# Relay_Scch.net
KiCad netlist of a schematic drawn in Altium Designer
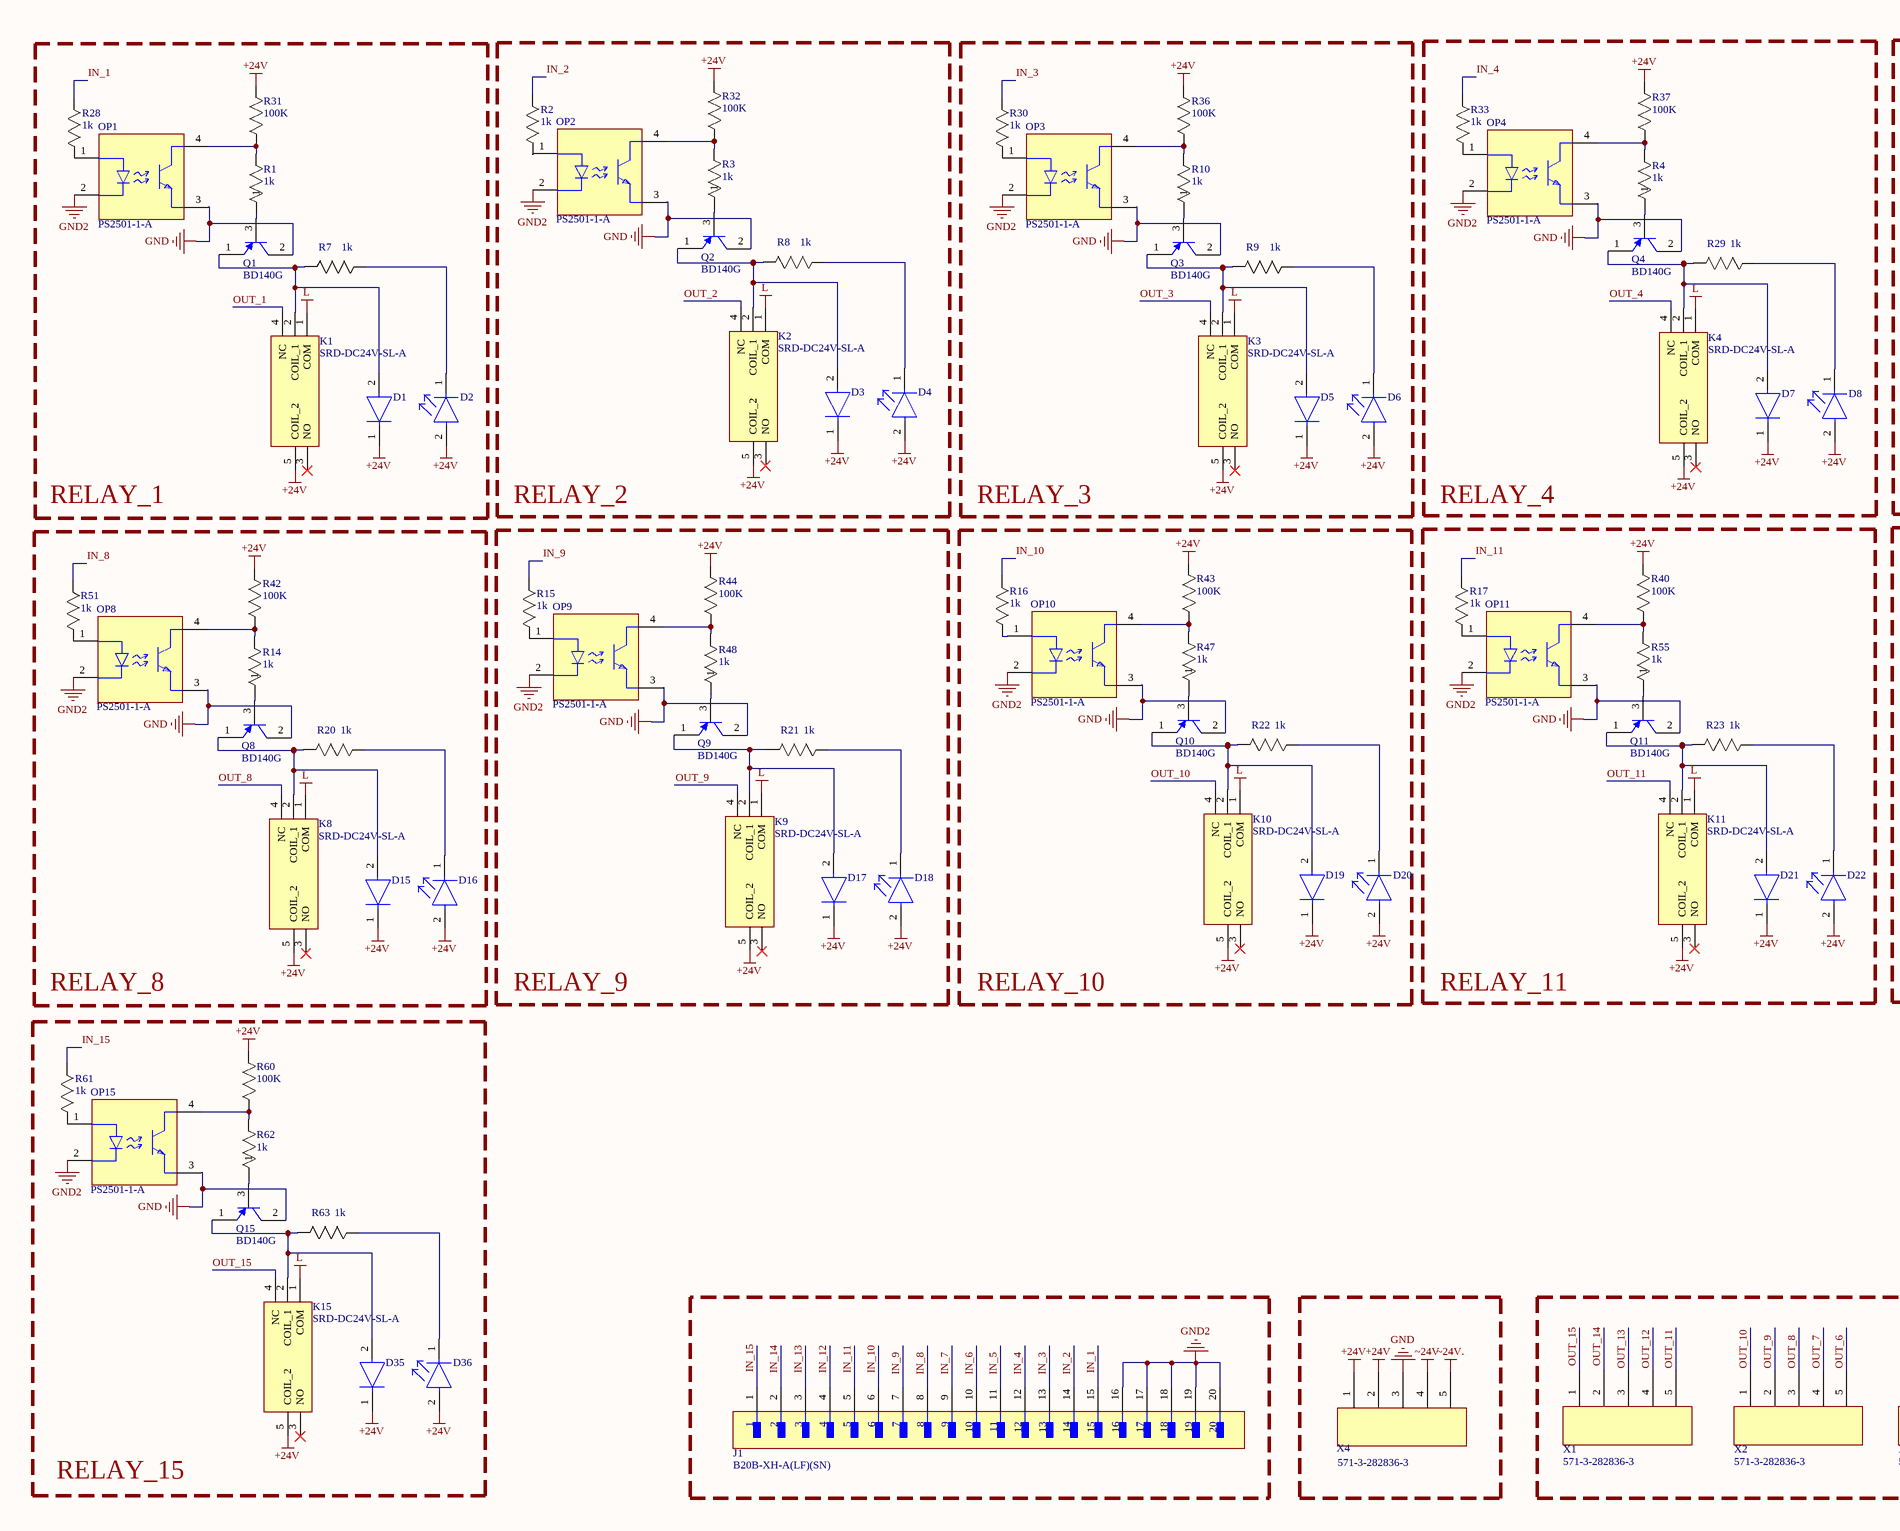
[diagram p0: Relay_Scch.SchDoc, left]
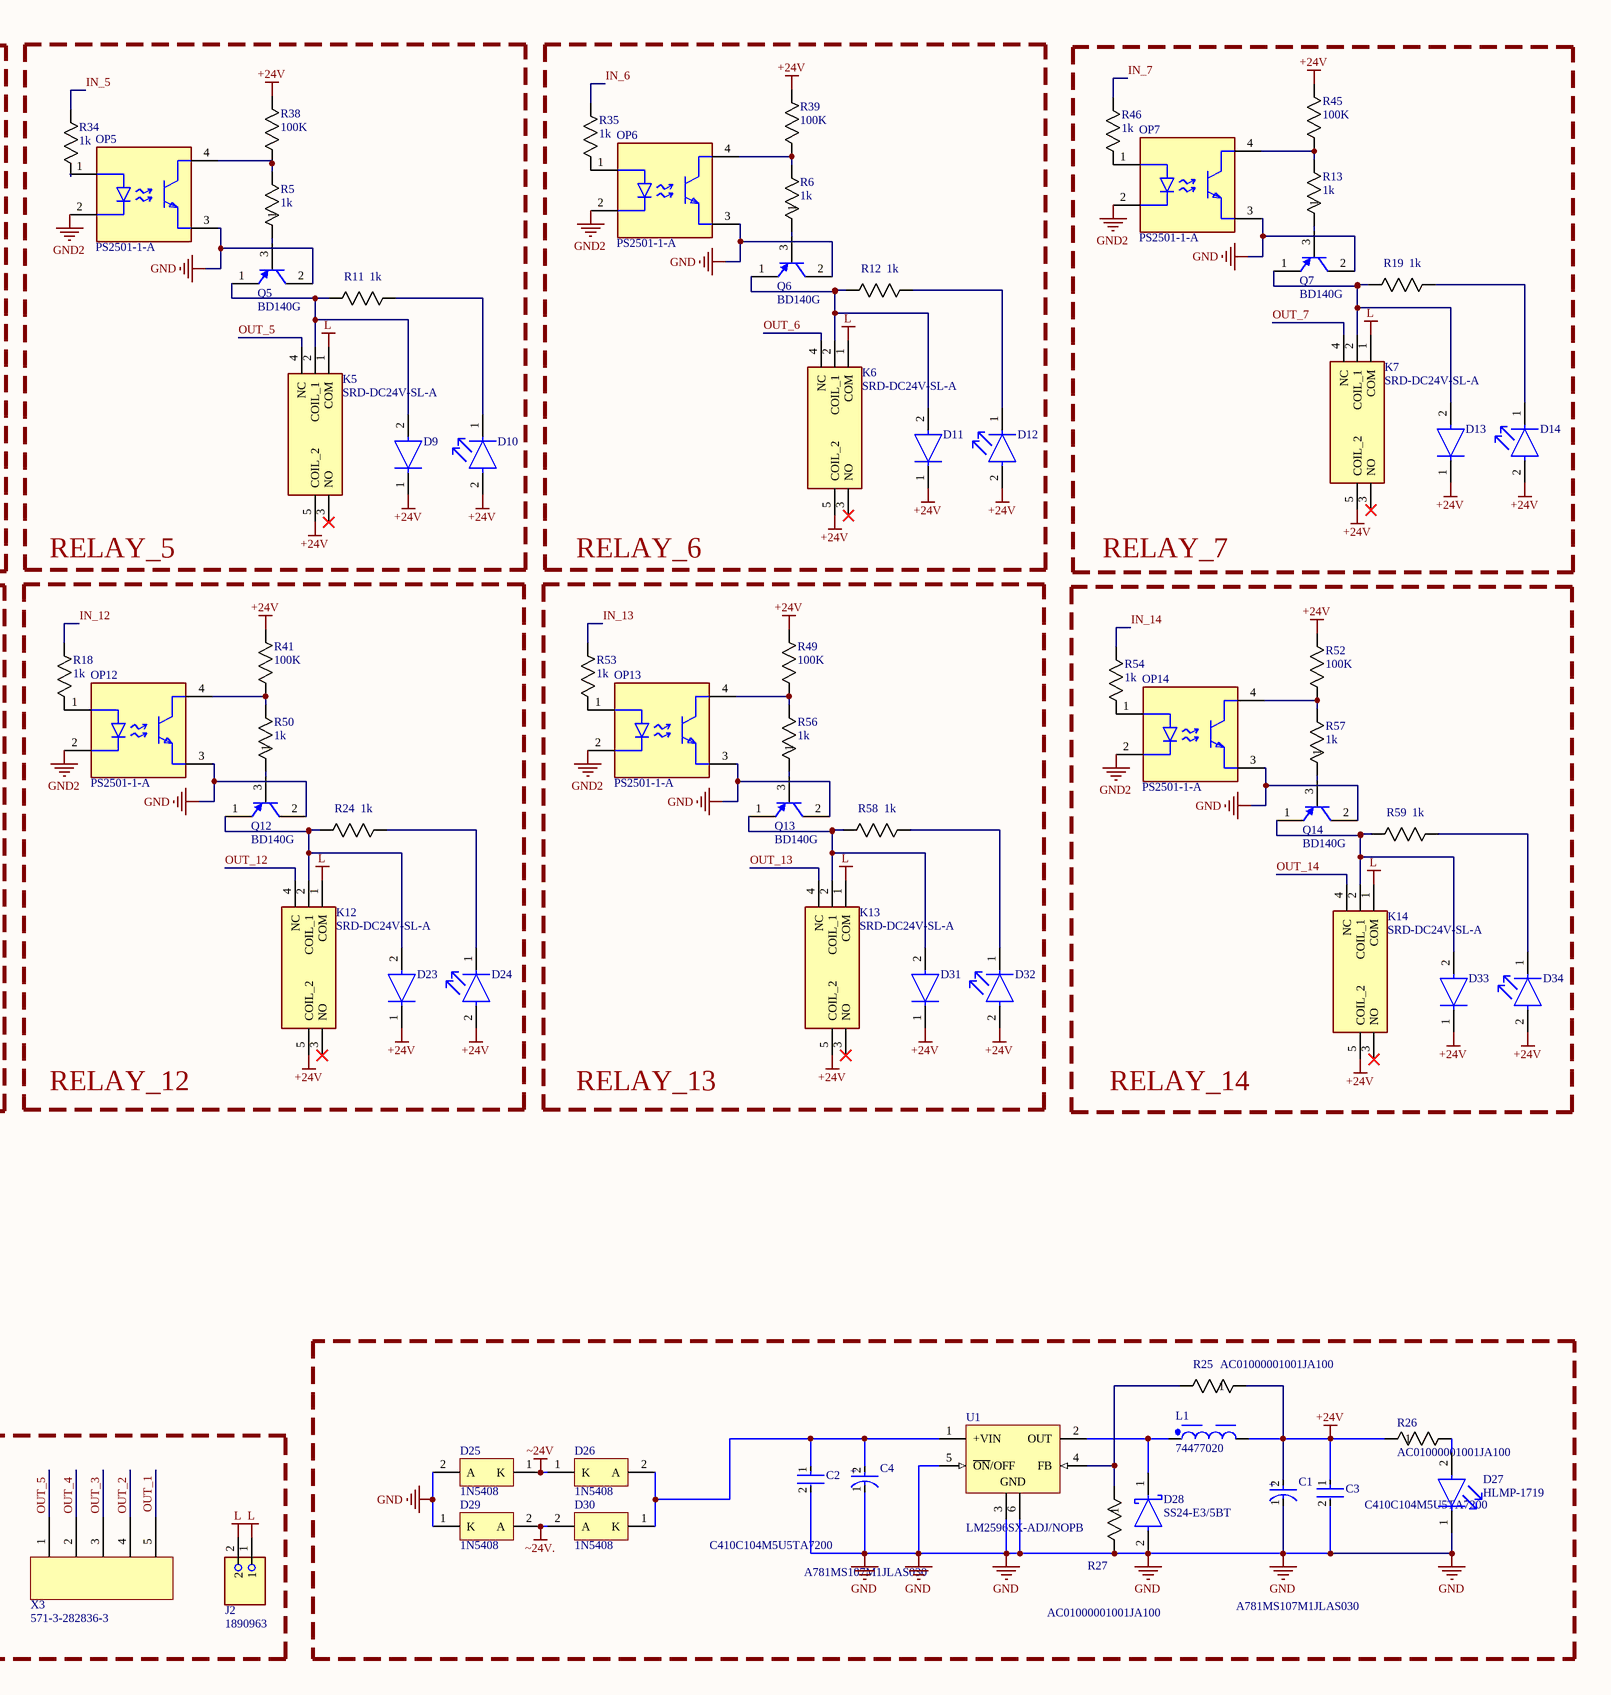
[diagram p1: Relay_Scch.SchDoc, right]

(export (version "E")
  (design (tool "Eeschema 10.0.6"))
  (components
    (comp (ref "C1")
      (value "A781MS107M1JLAS030")
      (footprint "FP-A781MS-S-MFG")
      (description "HYBRID POLYMER, V-CHIP, AEC-Q200")
      (libsource (lib "Altium Content Vault") (part "cf48714ba7e38822c1575c7ec0b6d1f"))
    )
    (comp (ref "C2")
      (value "C410C104M5U5TA7200")
      (footprint "FP-C410C104M5U5TA7200-MFG")
      (description "CAP CER 0.1UF 50V Z5U AXIAL")
      (fields (field (name "TOLERANCE") "20%"))
      (libsource (lib "Altium Content Vault") (part "b4654b650e69147ec39a6b967a45e02"))
    )
    (comp (ref "C3")
      (value "C410C104M5U5TA7200")
      (footprint "FP-C410C104M5U5TA7200-MFG")
      (description "CAP CER 0.1UF 50V Z5U AXIAL")
      (fields (field (name "TOLERANCE") "20%"))
      (libsource (lib "Altium Content Vault") (part "b4654b650e69147ec39a6b967a45e02"))
    )
    (comp (ref "C4")
      (value "A781MS107M1JLAS030")
      (footprint "FP-A781MS-S-MFG")
      (description "HYBRID POLYMER, V-CHIP, AEC-Q200")
      (libsource (lib "Altium Content Vault") (part "cf48714ba7e38822c1575c7ec0b6d1f"))
    )
    (comp (ref "D1")
      (value "1N4007")
      (footprint "FP-1N4007-MFG")
      (description "Rectifier diode 1000 V 1 A DO-41, ,")
      (fields
        (field (name "MANUFACTURER") "Diotec")
        (field (name "OCTOPART") "https://octopart.com/1n4007-diotec-4040411")
      )
      (libsource (lib "Altium Content Vault") (part "d7152d700b627762746794eb795d46e"))
    )
    (comp (ref "D2")
      (value "HLMP-1719")
      (footprint "FP-HLMP-1719-MFG")
      (description "LED YELLOW DIFFUSED T-1 T/H")
      (fields
        (field (name "MANUFACTURER") "Broadcom")
        (field (name "OCTOPART") "https://octopart.com/hlmp-1719-broadcom-71130405")
      )
      (libsource (lib "Altium Content Vault") (part "8706943c75ba83719d021d2fdc84c58"))
    )
    (comp (ref "D3")
      (value "1N4007")
      (footprint "FP-1N4007-MFG")
      (description "Rectifier diode 1000 V 1 A DO-41, ,")
      (fields
        (field (name "MANUFACTURER") "Diotec")
        (field (name "OCTOPART") "https://octopart.com/1n4007-diotec-4040411")
      )
      (libsource (lib "Altium Content Vault") (part "d7152d700b627762746794eb795d46e"))
    )
    (comp (ref "D4")
      (value "HLMP-1719")
      (footprint "FP-HLMP-1719-MFG")
      (description "LED YELLOW DIFFUSED T-1 T/H")
      (fields
        (field (name "MANUFACTURER") "Broadcom")
        (field (name "OCTOPART") "https://octopart.com/hlmp-1719-broadcom-71130405")
      )
      (libsource (lib "Altium Content Vault") (part "8706943c75ba83719d021d2fdc84c58"))
    )
    (comp (ref "D5")
      (value "1N4007")
      (footprint "FP-1N4007-MFG")
      (description "Rectifier diode 1000 V 1 A DO-41, ,")
      (fields
        (field (name "MANUFACTURER") "Diotec")
        (field (name "OCTOPART") "https://octopart.com/1n4007-diotec-4040411")
      )
      (libsource (lib "Altium Content Vault") (part "d7152d700b627762746794eb795d46e"))
    )
    (comp (ref "D6")
      (value "HLMP-1719")
      (footprint "FP-HLMP-1719-MFG")
      (description "LED YELLOW DIFFUSED T-1 T/H")
      (fields
        (field (name "MANUFACTURER") "Broadcom")
        (field (name "OCTOPART") "https://octopart.com/hlmp-1719-broadcom-71130405")
      )
      (libsource (lib "Altium Content Vault") (part "8706943c75ba83719d021d2fdc84c58"))
    )
    (comp (ref "D7")
      (value "1N4007")
      (footprint "FP-1N4007-MFG")
      (description "Rectifier diode 1000 V 1 A DO-41, ,")
      (fields
        (field (name "MANUFACTURER") "Diotec")
        (field (name "OCTOPART") "https://octopart.com/1n4007-diotec-4040411")
      )
      (libsource (lib "Altium Content Vault") (part "d7152d700b627762746794eb795d46e"))
    )
    (comp (ref "D8")
      (value "HLMP-1719")
      (footprint "FP-HLMP-1719-MFG")
      (description "LED YELLOW DIFFUSED T-1 T/H")
      (fields
        (field (name "MANUFACTURER") "Broadcom")
        (field (name "OCTOPART") "https://octopart.com/hlmp-1719-broadcom-71130405")
      )
      (libsource (lib "Altium Content Vault") (part "8706943c75ba83719d021d2fdc84c58"))
    )
    (comp (ref "D9")
      (value "1N4007")
      (footprint "FP-1N4007-MFG")
      (description "Rectifier diode 1000 V 1 A DO-41, ,")
      (fields
        (field (name "MANUFACTURER") "Diotec")
        (field (name "OCTOPART") "https://octopart.com/1n4007-diotec-4040411")
      )
      (libsource (lib "Altium Content Vault") (part "d7152d700b627762746794eb795d46e"))
    )
    (comp (ref "D10")
      (value "HLMP-1719")
      (footprint "FP-HLMP-1719-MFG")
      (description "LED YELLOW DIFFUSED T-1 T/H")
      (fields
        (field (name "MANUFACTURER") "Broadcom")
        (field (name "OCTOPART") "https://octopart.com/hlmp-1719-broadcom-71130405")
      )
      (libsource (lib "Altium Content Vault") (part "8706943c75ba83719d021d2fdc84c58"))
    )
    (comp (ref "D11")
      (value "1N4007")
      (footprint "FP-1N4007-MFG")
      (description "Rectifier diode 1000 V 1 A DO-41, ,")
      (fields
        (field (name "MANUFACTURER") "Diotec")
        (field (name "OCTOPART") "https://octopart.com/1n4007-diotec-4040411")
      )
      (libsource (lib "Altium Content Vault") (part "d7152d700b627762746794eb795d46e"))
    )
    (comp (ref "D12")
      (value "HLMP-1719")
      (footprint "FP-HLMP-1719-MFG")
      (description "LED YELLOW DIFFUSED T-1 T/H")
      (fields
        (field (name "MANUFACTURER") "Broadcom")
        (field (name "OCTOPART") "https://octopart.com/hlmp-1719-broadcom-71130405")
      )
      (libsource (lib "Altium Content Vault") (part "8706943c75ba83719d021d2fdc84c58"))
    )
    (comp (ref "D13")
      (value "1N4007")
      (footprint "FP-1N4007-MFG")
      (description "Rectifier diode 1000 V 1 A DO-41, ,")
      (fields
        (field (name "MANUFACTURER") "Diotec")
        (field (name "OCTOPART") "https://octopart.com/1n4007-diotec-4040411")
      )
      (libsource (lib "Altium Content Vault") (part "d7152d700b627762746794eb795d46e"))
    )
    (comp (ref "D14")
      (value "HLMP-1719")
      (footprint "FP-HLMP-1719-MFG")
      (description "LED YELLOW DIFFUSED T-1 T/H")
      (fields
        (field (name "MANUFACTURER") "Broadcom")
        (field (name "OCTOPART") "https://octopart.com/hlmp-1719-broadcom-71130405")
      )
      (libsource (lib "Altium Content Vault") (part "8706943c75ba83719d021d2fdc84c58"))
    )
    (comp (ref "D15")
      (value "1N4007")
      (footprint "FP-1N4007-MFG")
      (description "Rectifier diode 1000 V 1 A DO-41, ,")
      (fields
        (field (name "MANUFACTURER") "Diotec")
        (field (name "OCTOPART") "https://octopart.com/1n4007-diotec-4040411")
      )
      (libsource (lib "Altium Content Vault") (part "d7152d700b627762746794eb795d46e"))
    )
    (comp (ref "D16")
      (value "HLMP-1719")
      (footprint "FP-HLMP-1719-MFG")
      (description "LED YELLOW DIFFUSED T-1 T/H")
      (fields
        (field (name "MANUFACTURER") "Broadcom")
        (field (name "OCTOPART") "https://octopart.com/hlmp-1719-broadcom-71130405")
      )
      (libsource (lib "Altium Content Vault") (part "8706943c75ba83719d021d2fdc84c58"))
    )
    (comp (ref "D17")
      (value "1N4007")
      (footprint "FP-1N4007-MFG")
      (description "Rectifier diode 1000 V 1 A DO-41, ,")
      (fields
        (field (name "MANUFACTURER") "Diotec")
        (field (name "OCTOPART") "https://octopart.com/1n4007-diotec-4040411")
      )
      (libsource (lib "Altium Content Vault") (part "d7152d700b627762746794eb795d46e"))
    )
    (comp (ref "D18")
      (value "HLMP-1719")
      (footprint "FP-HLMP-1719-MFG")
      (description "LED YELLOW DIFFUSED T-1 T/H")
      (fields
        (field (name "MANUFACTURER") "Broadcom")
        (field (name "OCTOPART") "https://octopart.com/hlmp-1719-broadcom-71130405")
      )
      (libsource (lib "Altium Content Vault") (part "8706943c75ba83719d021d2fdc84c58"))
    )
    (comp (ref "D19")
      (value "1N4007")
      (footprint "FP-1N4007-MFG")
      (description "Rectifier diode 1000 V 1 A DO-41, ,")
      (fields
        (field (name "MANUFACTURER") "Diotec")
        (field (name "OCTOPART") "https://octopart.com/1n4007-diotec-4040411")
      )
      (libsource (lib "Altium Content Vault") (part "d7152d700b627762746794eb795d46e"))
    )
    (comp (ref "D20")
      (value "HLMP-1719")
      (footprint "FP-HLMP-1719-MFG")
      (description "LED YELLOW DIFFUSED T-1 T/H")
      (fields
        (field (name "MANUFACTURER") "Broadcom")
        (field (name "OCTOPART") "https://octopart.com/hlmp-1719-broadcom-71130405")
      )
      (libsource (lib "Altium Content Vault") (part "8706943c75ba83719d021d2fdc84c58"))
    )
    (comp (ref "D21")
      (value "1N4007")
      (footprint "FP-1N4007-MFG")
      (description "Rectifier diode 1000 V 1 A DO-41, ,")
      (fields
        (field (name "MANUFACTURER") "Diotec")
        (field (name "OCTOPART") "https://octopart.com/1n4007-diotec-4040411")
      )
      (libsource (lib "Altium Content Vault") (part "d7152d700b627762746794eb795d46e"))
    )
    (comp (ref "D22")
      (value "HLMP-1719")
      (footprint "FP-HLMP-1719-MFG")
      (description "LED YELLOW DIFFUSED T-1 T/H")
      (fields
        (field (name "MANUFACTURER") "Broadcom")
        (field (name "OCTOPART") "https://octopart.com/hlmp-1719-broadcom-71130405")
      )
      (libsource (lib "Altium Content Vault") (part "8706943c75ba83719d021d2fdc84c58"))
    )
    (comp (ref "D23")
      (value "1N4007")
      (footprint "FP-1N4007-MFG")
      (description "Rectifier diode 1000 V 1 A DO-41, ,")
      (fields
        (field (name "MANUFACTURER") "Diotec")
        (field (name "OCTOPART") "https://octopart.com/1n4007-diotec-4040411")
      )
      (libsource (lib "Altium Content Vault") (part "d7152d700b627762746794eb795d46e"))
    )
    (comp (ref "D24")
      (value "HLMP-1719")
      (footprint "FP-HLMP-1719-MFG")
      (description "LED YELLOW DIFFUSED T-1 T/H")
      (fields
        (field (name "MANUFACTURER") "Broadcom")
        (field (name "OCTOPART") "https://octopart.com/hlmp-1719-broadcom-71130405")
      )
      (libsource (lib "Altium Content Vault") (part "8706943c75ba83719d021d2fdc84c58"))
    )
    (comp (ref "D25")
      (value "1N5408")
      (footprint "ONSC-AXIAL_LEAD-2-267-05_V")
      (description "Standard Recovery Rectifier, 2-Pin Axial_Lead, Pb-Free, Bulk Box")
      (fields (field (name "MANUFACTURER") "On Semiconductor"))
      (libsource (lib "") (part "ONSC-D-K1A2-2_A_1"))
    )
    (comp (ref "D26")
      (value "1N5408")
      (footprint "ONSC-AXIAL_LEAD-2-267-05_V")
      (description "Standard Recovery Rectifier, 2-Pin Axial_Lead, Pb-Free, Bulk Box")
      (fields (field (name "MANUFACTURER") "On Semiconductor"))
      (libsource (lib "Altium Content Vault") (part "ONSC-D-K1A2-2_A"))
    )
    (comp (ref "D27")
      (value "HLMP-1719")
      (footprint "FP-HLMP-1719-MFG")
      (description "LED YELLOW DIFFUSED T-1 T/H")
      (fields
        (field (name "MANUFACTURER") "Broadcom")
        (field (name "OCTOPART") "https://octopart.com/hlmp-1719-broadcom-71130405")
      )
      (libsource (lib "Altium Content Vault") (part "8706943c75ba83719d021d2fdc84c58"))
    )
    (comp (ref "D28")
      (value "SS24-E3/5BT")
      (footprint "FP-95401-MFG")
      (description "SS24-E3/5BT Rectifier Diode, Schottky, 1 Phase, 1 Element, 2A, 40V V(RRM), Silicon, DO-214AA")
      (libsource (lib "Altium Content Vault") (part "c1678fac7984e62e0809fbf79c06691"))
    )
    (comp (ref "D29")
      (value "1N5408")
      (footprint "ONSC-AXIAL_LEAD-2-267-05_V")
      (description "Standard Recovery Rectifier, 2-Pin Axial_Lead, Pb-Free, Bulk Box")
      (fields (field (name "MANUFACTURER") "On Semiconductor"))
      (libsource (lib "Altium Content Vault") (part "ONSC-D-K1A2-2_A"))
    )
    (comp (ref "D30")
      (value "1N5408")
      (footprint "ONSC-AXIAL_LEAD-2-267-05_V")
      (description "Standard Recovery Rectifier, 2-Pin Axial_Lead, Pb-Free, Bulk Box")
      (fields (field (name "MANUFACTURER") "On Semiconductor"))
      (libsource (lib "") (part "ONSC-D-K1A2-2_A_1"))
    )
    (comp (ref "D31")
      (value "1N4007")
      (footprint "FP-1N4007-MFG")
      (description "Rectifier diode 1000 V 1 A DO-41, ,")
      (fields
        (field (name "MANUFACTURER") "Diotec")
        (field (name "OCTOPART") "https://octopart.com/1n4007-diotec-4040411")
      )
      (libsource (lib "Altium Content Vault") (part "d7152d700b627762746794eb795d46e"))
    )
    (comp (ref "D32")
      (value "HLMP-1719")
      (footprint "FP-HLMP-1719-MFG")
      (description "LED YELLOW DIFFUSED T-1 T/H")
      (fields
        (field (name "MANUFACTURER") "Broadcom")
        (field (name "OCTOPART") "https://octopart.com/hlmp-1719-broadcom-71130405")
      )
      (libsource (lib "Altium Content Vault") (part "8706943c75ba83719d021d2fdc84c58"))
    )
    (comp (ref "D33")
      (value "1N4007")
      (footprint "FP-1N4007-MFG")
      (description "Rectifier diode 1000 V 1 A DO-41, ,")
      (fields
        (field (name "MANUFACTURER") "Diotec")
        (field (name "OCTOPART") "https://octopart.com/1n4007-diotec-4040411")
      )
      (libsource (lib "Altium Content Vault") (part "d7152d700b627762746794eb795d46e"))
    )
    (comp (ref "D34")
      (value "HLMP-1719")
      (footprint "FP-HLMP-1719-MFG")
      (description "LED YELLOW DIFFUSED T-1 T/H")
      (fields
        (field (name "MANUFACTURER") "Broadcom")
        (field (name "OCTOPART") "https://octopart.com/hlmp-1719-broadcom-71130405")
      )
      (libsource (lib "Altium Content Vault") (part "8706943c75ba83719d021d2fdc84c58"))
    )
    (comp (ref "D35")
      (value "1N4007")
      (footprint "FP-1N4007-MFG")
      (description "Rectifier diode 1000 V 1 A DO-41, ,")
      (fields
        (field (name "MANUFACTURER") "Diotec")
        (field (name "OCTOPART") "https://octopart.com/1n4007-diotec-4040411")
      )
      (libsource (lib "Altium Content Vault") (part "d7152d700b627762746794eb795d46e"))
    )
    (comp (ref "D36")
      (value "HLMP-1719")
      (footprint "FP-HLMP-1719-MFG")
      (description "LED YELLOW DIFFUSED T-1 T/H")
      (fields
        (field (name "MANUFACTURER") "Broadcom")
        (field (name "OCTOPART") "https://octopart.com/hlmp-1719-broadcom-71130405")
      )
      (libsource (lib "Altium Content Vault") (part "8706943c75ba83719d021d2fdc84c58"))
    )
    (comp (ref "J1")
      (value "B20B-XH-A(LF)(SN)")
      (footprint "FP-B20B-XH-A_LF_SN-MFG")
      (description "CONN HEADER VERT 20POS 2.5MM")
      (libsource (lib "Altium Content Vault") (part "fe5080d2b0106897c8c372ff840dfff"))
    )
    (comp (ref "J2")
      (value "1890963")
      (footprint "PHOENIX_1890963")
      (libsource (lib "1890963") (part "1890963"))
    )
    (comp (ref "K1")
      (value "SRD-DC24V-SL-A")
      (footprint "srd24vdcslc")
      (description "Relay or Contactor")
      (fields (field (name "MANUFACTURER_PART_NUMBER") "srd-24vdc-sl-c"))
      (libsource (lib "Relay Aram") (part "srd-24vdc-sl-c"))
    )
    (comp (ref "K2")
      (value "SRD-DC24V-SL-A")
      (footprint "srd24vdcslc")
      (description "Relay or Contactor")
      (fields (field (name "MANUFACTURER_PART_NUMBER") "srd-24vdc-sl-c"))
      (libsource (lib "Relay Aram") (part "srd-24vdc-sl-c"))
    )
    (comp (ref "K3")
      (value "SRD-DC24V-SL-A")
      (footprint "srd24vdcslc")
      (description "Relay or Contactor")
      (fields (field (name "MANUFACTURER_PART_NUMBER") "srd-24vdc-sl-c"))
      (libsource (lib "Relay Aram") (part "srd-24vdc-sl-c"))
    )
    (comp (ref "K4")
      (value "SRD-DC24V-SL-A")
      (footprint "srd24vdcslc")
      (description "Relay or Contactor")
      (fields (field (name "MANUFACTURER_PART_NUMBER") "srd-24vdc-sl-c"))
      (libsource (lib "Relay Aram") (part "srd-24vdc-sl-c"))
    )
    (comp (ref "K5")
      (value "SRD-DC24V-SL-A")
      (footprint "srd24vdcslc")
      (description "Relay or Contactor")
      (fields (field (name "MANUFACTURER_PART_NUMBER") "srd-24vdc-sl-c"))
      (libsource (lib "Relay Aram") (part "srd-24vdc-sl-c"))
    )
    (comp (ref "K6")
      (value "SRD-DC24V-SL-A")
      (footprint "srd24vdcslc")
      (description "Relay or Contactor")
      (fields (field (name "MANUFACTURER_PART_NUMBER") "srd-24vdc-sl-c"))
      (libsource (lib "Relay Aram") (part "srd-24vdc-sl-c"))
    )
    (comp (ref "K7")
      (value "SRD-DC24V-SL-A")
      (footprint "srd24vdcslc")
      (description "Relay or Contactor")
      (fields (field (name "MANUFACTURER_PART_NUMBER") "srd-24vdc-sl-c"))
      (libsource (lib "Relay Aram") (part "srd-24vdc-sl-c"))
    )
    (comp (ref "K8")
      (value "SRD-DC24V-SL-A")
      (footprint "srd24vdcslc")
      (description "Relay or Contactor")
      (fields (field (name "MANUFACTURER_PART_NUMBER") "srd-24vdc-sl-c"))
      (libsource (lib "Relay Aram") (part "srd-24vdc-sl-c"))
    )
    (comp (ref "K9")
      (value "SRD-DC24V-SL-A")
      (footprint "srd24vdcslc")
      (description "Relay or Contactor")
      (fields (field (name "MANUFACTURER_PART_NUMBER") "srd-24vdc-sl-c"))
      (libsource (lib "Relay Aram") (part "srd-24vdc-sl-c"))
    )
    (comp (ref "K10")
      (value "SRD-DC24V-SL-A")
      (footprint "srd24vdcslc")
      (description "Relay or Contactor")
      (fields (field (name "MANUFACTURER_PART_NUMBER") "srd-24vdc-sl-c"))
      (libsource (lib "Relay Aram") (part "srd-24vdc-sl-c"))
    )
    (comp (ref "K11")
      (value "SRD-DC24V-SL-A")
      (footprint "srd24vdcslc")
      (description "Relay or Contactor")
      (fields (field (name "MANUFACTURER_PART_NUMBER") "srd-24vdc-sl-c"))
      (libsource (lib "Relay Aram") (part "srd-24vdc-sl-c"))
    )
    (comp (ref "K12")
      (value "SRD-DC24V-SL-A")
      (footprint "srd24vdcslc")
      (description "Relay or Contactor")
      (fields (field (name "MANUFACTURER_PART_NUMBER") "srd-24vdc-sl-c"))
      (libsource (lib "Relay Aram") (part "srd-24vdc-sl-c"))
    )
    (comp (ref "K13")
      (value "SRD-DC24V-SL-A")
      (footprint "srd24vdcslc")
      (description "Relay or Contactor")
      (fields (field (name "MANUFACTURER_PART_NUMBER") "srd-24vdc-sl-c"))
      (libsource (lib "Relay Aram") (part "srd-24vdc-sl-c"))
    )
    (comp (ref "K14")
      (value "SRD-DC24V-SL-A")
      (footprint "srd24vdcslc")
      (description "Relay or Contactor")
      (fields (field (name "MANUFACTURER_PART_NUMBER") "srd-24vdc-sl-c"))
      (libsource (lib "Relay Aram") (part "srd-24vdc-sl-c"))
    )
    (comp (ref "K15")
      (value "SRD-DC24V-SL-A")
      (footprint "srd24vdcslc")
      (description "Relay or Contactor")
      (fields (field (name "MANUFACTURER_PART_NUMBER") "srd-24vdc-sl-c"))
      (libsource (lib "Relay Aram") (part "srd-24vdc-sl-c"))
    )
    (comp (ref "L1")
      (value "74477020")
      (footprint "WE-PD_1280")
      (fields (field (name "TOLERANCE") "20%"))
      (libsource (lib "Altium Content Vault") (part "Inductor - 2"))
    )
    (comp (ref "OP1")
      (value "PS2501-1-A")
      (footprint "FP-PS2501-1-A-MFG")
      (description "OPTOISOLATOR 5KV TRANS 4DIP")
      (libsource (lib "Altium Content Vault") (part "9c0182559cfc66618ddd85553301ae2"))
    )
    (comp (ref "OP2")
      (value "PS2501-1-A")
      (footprint "FP-PS2501-1-A-MFG")
      (description "OPTOISOLATOR 5KV TRANS 4DIP")
      (libsource (lib "Altium Content Vault") (part "9c0182559cfc66618ddd85553301ae2"))
    )
    (comp (ref "OP3")
      (value "PS2501-1-A")
      (footprint "FP-PS2501-1-A-MFG")
      (description "OPTOISOLATOR 5KV TRANS 4DIP")
      (libsource (lib "Altium Content Vault") (part "9c0182559cfc66618ddd85553301ae2"))
    )
    (comp (ref "OP4")
      (value "PS2501-1-A")
      (footprint "FP-PS2501-1-A-MFG")
      (description "OPTOISOLATOR 5KV TRANS 4DIP")
      (libsource (lib "Altium Content Vault") (part "9c0182559cfc66618ddd85553301ae2"))
    )
    (comp (ref "OP5")
      (value "PS2501-1-A")
      (footprint "FP-PS2501-1-A-MFG")
      (description "OPTOISOLATOR 5KV TRANS 4DIP")
      (libsource (lib "Altium Content Vault") (part "9c0182559cfc66618ddd85553301ae2"))
    )
    (comp (ref "OP6")
      (value "PS2501-1-A")
      (footprint "FP-PS2501-1-A-MFG")
      (description "OPTOISOLATOR 5KV TRANS 4DIP")
      (libsource (lib "Altium Content Vault") (part "9c0182559cfc66618ddd85553301ae2"))
    )
    (comp (ref "OP7")
      (value "PS2501-1-A")
      (footprint "FP-PS2501-1-A-MFG")
      (description "OPTOISOLATOR 5KV TRANS 4DIP")
      (libsource (lib "Altium Content Vault") (part "9c0182559cfc66618ddd85553301ae2"))
    )
    (comp (ref "OP8")
      (value "PS2501-1-A")
      (footprint "FP-PS2501-1-A-MFG")
      (description "OPTOISOLATOR 5KV TRANS 4DIP")
      (libsource (lib "Altium Content Vault") (part "9c0182559cfc66618ddd85553301ae2"))
    )
    (comp (ref "OP9")
      (value "PS2501-1-A")
      (footprint "FP-PS2501-1-A-MFG")
      (description "OPTOISOLATOR 5KV TRANS 4DIP")
      (libsource (lib "Altium Content Vault") (part "9c0182559cfc66618ddd85553301ae2"))
    )
    (comp (ref "OP10")
      (value "PS2501-1-A")
      (footprint "FP-PS2501-1-A-MFG")
      (description "OPTOISOLATOR 5KV TRANS 4DIP")
      (libsource (lib "Altium Content Vault") (part "9c0182559cfc66618ddd85553301ae2"))
    )
    (comp (ref "OP11")
      (value "PS2501-1-A")
      (footprint "FP-PS2501-1-A-MFG")
      (description "OPTOISOLATOR 5KV TRANS 4DIP")
      (libsource (lib "Altium Content Vault") (part "9c0182559cfc66618ddd85553301ae2"))
    )
    (comp (ref "OP12")
      (value "PS2501-1-A")
      (footprint "FP-PS2501-1-A-MFG")
      (description "OPTOISOLATOR 5KV TRANS 4DIP")
      (libsource (lib "Altium Content Vault") (part "9c0182559cfc66618ddd85553301ae2"))
    )
    (comp (ref "OP13")
      (value "PS2501-1-A")
      (footprint "FP-PS2501-1-A-MFG")
      (description "OPTOISOLATOR 5KV TRANS 4DIP")
      (libsource (lib "Altium Content Vault") (part "9c0182559cfc66618ddd85553301ae2"))
    )
    (comp (ref "OP14")
      (value "PS2501-1-A")
      (footprint "FP-PS2501-1-A-MFG")
      (description "OPTOISOLATOR 5KV TRANS 4DIP")
      (libsource (lib "Altium Content Vault") (part "9c0182559cfc66618ddd85553301ae2"))
    )
    (comp (ref "OP15")
      (value "PS2501-1-A")
      (footprint "FP-PS2501-1-A-MFG")
      (description "OPTOISOLATOR 5KV TRANS 4DIP")
      (libsource (lib "Altium Content Vault") (part "9c0182559cfc66618ddd85553301ae2"))
    )
    (comp (ref "Q1")
      (value "BD140G")
      (footprint "ONSC-TO-225-3-77-09")
      (description "Plastic Medium-Power Silicon PNP Transistor, 3-Pin TO-225, Pb-Free, Bulk Box")
      (fields (field (name "MANUFACTURER") "ON Semiconductor"))
      (libsource (lib "Relay Aram") (part "CMP-1048-01270-1"))
    )
    (comp (ref "Q2")
      (value "BD140G")
      (footprint "ONSC-TO-225-3-77-09")
      (description "Plastic Medium-Power Silicon PNP Transistor, 3-Pin TO-225, Pb-Free, Bulk Box")
      (fields (field (name "MANUFACTURER") "ON Semiconductor"))
      (libsource (lib "Relay Aram") (part "CMP-1048-01270-1"))
    )
    (comp (ref "Q3")
      (value "BD140G")
      (footprint "ONSC-TO-225-3-77-09")
      (description "Plastic Medium-Power Silicon PNP Transistor, 3-Pin TO-225, Pb-Free, Bulk Box")
      (fields (field (name "MANUFACTURER") "ON Semiconductor"))
      (libsource (lib "Relay Aram") (part "CMP-1048-01270-1"))
    )
    (comp (ref "Q4")
      (value "BD140G")
      (footprint "ONSC-TO-225-3-77-09")
      (description "Plastic Medium-Power Silicon PNP Transistor, 3-Pin TO-225, Pb-Free, Bulk Box")
      (fields (field (name "MANUFACTURER") "ON Semiconductor"))
      (libsource (lib "Relay Aram") (part "CMP-1048-01270-1"))
    )
    (comp (ref "Q5")
      (value "BD140G")
      (footprint "ONSC-TO-225-3-77-09")
      (description "Plastic Medium-Power Silicon PNP Transistor, 3-Pin TO-225, Pb-Free, Bulk Box")
      (fields (field (name "MANUFACTURER") "ON Semiconductor"))
      (libsource (lib "Relay Aram") (part "CMP-1048-01270-1"))
    )
    (comp (ref "Q6")
      (value "BD140G")
      (footprint "ONSC-TO-225-3-77-09")
      (description "Plastic Medium-Power Silicon PNP Transistor, 3-Pin TO-225, Pb-Free, Bulk Box")
      (fields (field (name "MANUFACTURER") "ON Semiconductor"))
      (libsource (lib "Relay Aram") (part "CMP-1048-01270-1"))
    )
    (comp (ref "Q7")
      (value "BD140G")
      (footprint "ONSC-TO-225-3-77-09")
      (description "Plastic Medium-Power Silicon PNP Transistor, 3-Pin TO-225, Pb-Free, Bulk Box")
      (fields (field (name "MANUFACTURER") "ON Semiconductor"))
      (libsource (lib "Relay Aram") (part "CMP-1048-01270-1"))
    )
    (comp (ref "Q8")
      (value "BD140G")
      (footprint "ONSC-TO-225-3-77-09")
      (description "Plastic Medium-Power Silicon PNP Transistor, 3-Pin TO-225, Pb-Free, Bulk Box")
      (fields (field (name "MANUFACTURER") "ON Semiconductor"))
      (libsource (lib "Relay Aram") (part "CMP-1048-01270-1"))
    )
    (comp (ref "Q9")
      (value "BD140G")
      (footprint "ONSC-TO-225-3-77-09")
      (description "Plastic Medium-Power Silicon PNP Transistor, 3-Pin TO-225, Pb-Free, Bulk Box")
      (fields (field (name "MANUFACTURER") "ON Semiconductor"))
      (libsource (lib "Relay Aram") (part "CMP-1048-01270-1"))
    )
    (comp (ref "Q10")
      (value "BD140G")
      (footprint "ONSC-TO-225-3-77-09")
      (description "Plastic Medium-Power Silicon PNP Transistor, 3-Pin TO-225, Pb-Free, Bulk Box")
      (fields (field (name "MANUFACTURER") "ON Semiconductor"))
      (libsource (lib "Relay Aram") (part "CMP-1048-01270-1"))
    )
    (comp (ref "Q11")
      (value "BD140G")
      (footprint "ONSC-TO-225-3-77-09")
      (description "Plastic Medium-Power Silicon PNP Transistor, 3-Pin TO-225, Pb-Free, Bulk Box")
      (fields (field (name "MANUFACTURER") "ON Semiconductor"))
      (libsource (lib "Relay Aram") (part "CMP-1048-01270-1"))
    )
    (comp (ref "Q12")
      (value "BD140G")
      (footprint "ONSC-TO-225-3-77-09")
      (description "Plastic Medium-Power Silicon PNP Transistor, 3-Pin TO-225, Pb-Free, Bulk Box")
      (fields (field (name "MANUFACTURER") "ON Semiconductor"))
      (libsource (lib "Relay Aram") (part "CMP-1048-01270-1"))
    )
    (comp (ref "Q13")
      (value "BD140G")
      (footprint "ONSC-TO-225-3-77-09")
      (description "Plastic Medium-Power Silicon PNP Transistor, 3-Pin TO-225, Pb-Free, Bulk Box")
      (fields (field (name "MANUFACTURER") "ON Semiconductor"))
      (libsource (lib "Relay Aram") (part "CMP-1048-01270-1"))
    )
    (comp (ref "Q14")
      (value "BD140G")
      (footprint "ONSC-TO-225-3-77-09")
      (description "Plastic Medium-Power Silicon PNP Transistor, 3-Pin TO-225, Pb-Free, Bulk Box")
      (fields (field (name "MANUFACTURER") "ON Semiconductor"))
      (libsource (lib "Relay Aram") (part "CMP-1048-01270-1"))
    )
    (comp (ref "Q15")
      (value "BD140G")
      (footprint "ONSC-TO-225-3-77-09")
      (description "Plastic Medium-Power Silicon PNP Transistor, 3-Pin TO-225, Pb-Free, Bulk Box")
      (fields (field (name "MANUFACTURER") "ON Semiconductor"))
      (libsource (lib "Relay Aram") (part "CMP-1048-01270-1"))
    )
    (comp (ref "R1")
      (value "1k")
      (footprint "RES_AC01_VIS")
      (description "VISHAY AC01000001001JA100 Through Hole Resistor, 1 kohm, Axial Leaded, 1 W, 5%, AC Series")
      (fields (field (name "TOLERANCE") "5%"))
      (libsource (lib "") (part "AC01000001001JA100_1"))
    )
    (comp (ref "R2")
      (value "1k")
      (footprint "RES_AC01_VIS")
      (description "VISHAY AC01000001001JA100 Through Hole Resistor, 1 kohm, Axial Leaded, 1 W, 5%, AC Series")
      (fields (field (name "TOLERANCE") "5%"))
      (libsource (lib "Altium Content Vault") (part "AC01000001001JA100"))
    )
    (comp (ref "R3")
      (value "1k")
      (footprint "RES_AC01_VIS")
      (description "VISHAY AC01000001001JA100 Through Hole Resistor, 1 kohm, Axial Leaded, 1 W, 5%, AC Series")
      (fields (field (name "TOLERANCE") "5%"))
      (libsource (lib "") (part "AC01000001001JA100_1"))
    )
    (comp (ref "R4")
      (value "1k")
      (footprint "RES_AC01_VIS")
      (description "VISHAY AC01000001001JA100 Through Hole Resistor, 1 kohm, Axial Leaded, 1 W, 5%, AC Series")
      (fields (field (name "TOLERANCE") "5%"))
      (libsource (lib "") (part "AC01000001001JA100_1"))
    )
    (comp (ref "R5")
      (value "1k")
      (footprint "RES_AC01_VIS")
      (description "VISHAY AC01000001001JA100 Through Hole Resistor, 1 kohm, Axial Leaded, 1 W, 5%, AC Series")
      (fields (field (name "TOLERANCE") "5%"))
      (libsource (lib "") (part "AC01000001001JA100_1"))
    )
    (comp (ref "R6")
      (value "1k")
      (footprint "RES_AC01_VIS")
      (description "VISHAY AC01000001001JA100 Through Hole Resistor, 1 kohm, Axial Leaded, 1 W, 5%, AC Series")
      (fields (field (name "TOLERANCE") "5%"))
      (libsource (lib "") (part "AC01000001001JA100_1"))
    )
    (comp (ref "R7")
      (value "1k")
      (footprint "RES_AC01_VIS")
      (description "VISHAY AC01000001001JA100 Through Hole Resistor, 1 kohm, Axial Leaded, 1 W, 5%, AC Series")
      (fields (field (name "TOLERANCE") "5%"))
      (libsource (lib "Altium Content Vault") (part "AC01000001001JA100"))
    )
    (comp (ref "R8")
      (value "1k")
      (footprint "RES_AC01_VIS")
      (description "VISHAY AC01000001001JA100 Through Hole Resistor, 1 kohm, Axial Leaded, 1 W, 5%, AC Series")
      (fields (field (name "TOLERANCE") "5%"))
      (libsource (lib "Altium Content Vault") (part "AC01000001001JA100"))
    )
    (comp (ref "R9")
      (value "1k")
      (footprint "RES_AC01_VIS")
      (description "VISHAY AC01000001001JA100 Through Hole Resistor, 1 kohm, Axial Leaded, 1 W, 5%, AC Series")
      (fields (field (name "TOLERANCE") "5%"))
      (libsource (lib "Altium Content Vault") (part "AC01000001001JA100"))
    )
    (comp (ref "R10")
      (value "1k")
      (footprint "RES_AC01_VIS")
      (description "VISHAY AC01000001001JA100 Through Hole Resistor, 1 kohm, Axial Leaded, 1 W, 5%, AC Series")
      (fields (field (name "TOLERANCE") "5%"))
      (libsource (lib "") (part "AC01000001001JA100_1"))
    )
    (comp (ref "R11")
      (value "1k")
      (footprint "RES_AC01_VIS")
      (description "VISHAY AC01000001001JA100 Through Hole Resistor, 1 kohm, Axial Leaded, 1 W, 5%, AC Series")
      (fields (field (name "TOLERANCE") "5%"))
      (libsource (lib "Altium Content Vault") (part "AC01000001001JA100"))
    )
    (comp (ref "R12")
      (value "1k")
      (footprint "RES_AC01_VIS")
      (description "VISHAY AC01000001001JA100 Through Hole Resistor, 1 kohm, Axial Leaded, 1 W, 5%, AC Series")
      (fields (field (name "TOLERANCE") "5%"))
      (libsource (lib "Altium Content Vault") (part "AC01000001001JA100"))
    )
    (comp (ref "R13")
      (value "1k")
      (footprint "RES_AC01_VIS")
      (description "VISHAY AC01000001001JA100 Through Hole Resistor, 1 kohm, Axial Leaded, 1 W, 5%, AC Series")
      (fields (field (name "TOLERANCE") "5%"))
      (libsource (lib "") (part "AC01000001001JA100_1"))
    )
    (comp (ref "R14")
      (value "1k")
      (footprint "RES_AC01_VIS")
      (description "VISHAY AC01000001001JA100 Through Hole Resistor, 1 kohm, Axial Leaded, 1 W, 5%, AC Series")
      (fields (field (name "TOLERANCE") "5%"))
      (libsource (lib "") (part "AC01000001001JA100_1"))
    )
    (comp (ref "R15")
      (value "1k")
      (footprint "RES_AC01_VIS")
      (description "VISHAY AC01000001001JA100 Through Hole Resistor, 1 kohm, Axial Leaded, 1 W, 5%, AC Series")
      (fields (field (name "TOLERANCE") "5%"))
      (libsource (lib "Altium Content Vault") (part "AC01000001001JA100"))
    )
    (comp (ref "R16")
      (value "1k")
      (footprint "RES_AC01_VIS")
      (description "VISHAY AC01000001001JA100 Through Hole Resistor, 1 kohm, Axial Leaded, 1 W, 5%, AC Series")
      (fields (field (name "TOLERANCE") "5%"))
      (libsource (lib "Altium Content Vault") (part "AC01000001001JA100"))
    )
    (comp (ref "R17")
      (value "1k")
      (footprint "RES_AC01_VIS")
      (description "VISHAY AC01000001001JA100 Through Hole Resistor, 1 kohm, Axial Leaded, 1 W, 5%, AC Series")
      (fields (field (name "TOLERANCE") "5%"))
      (libsource (lib "Altium Content Vault") (part "AC01000001001JA100"))
    )
    (comp (ref "R18")
      (value "1k")
      (footprint "RES_AC01_VIS")
      (description "VISHAY AC01000001001JA100 Through Hole Resistor, 1 kohm, Axial Leaded, 1 W, 5%, AC Series")
      (fields (field (name "TOLERANCE") "5%"))
      (libsource (lib "Altium Content Vault") (part "AC01000001001JA100"))
    )
    (comp (ref "R19")
      (value "1k")
      (footprint "RES_AC01_VIS")
      (description "VISHAY AC01000001001JA100 Through Hole Resistor, 1 kohm, Axial Leaded, 1 W, 5%, AC Series")
      (fields (field (name "TOLERANCE") "5%"))
      (libsource (lib "Altium Content Vault") (part "AC01000001001JA100"))
    )
    (comp (ref "R20")
      (value "1k")
      (footprint "RES_AC01_VIS")
      (description "VISHAY AC01000001001JA100 Through Hole Resistor, 1 kohm, Axial Leaded, 1 W, 5%, AC Series")
      (fields (field (name "TOLERANCE") "5%"))
      (libsource (lib "Altium Content Vault") (part "AC01000001001JA100"))
    )
    (comp (ref "R21")
      (value "1k")
      (footprint "RES_AC01_VIS")
      (description "VISHAY AC01000001001JA100 Through Hole Resistor, 1 kohm, Axial Leaded, 1 W, 5%, AC Series")
      (fields (field (name "TOLERANCE") "5%"))
      (libsource (lib "Altium Content Vault") (part "AC01000001001JA100"))
    )
    (comp (ref "R22")
      (value "1k")
      (footprint "RES_AC01_VIS")
      (description "VISHAY AC01000001001JA100 Through Hole Resistor, 1 kohm, Axial Leaded, 1 W, 5%, AC Series")
      (fields (field (name "TOLERANCE") "5%"))
      (libsource (lib "Altium Content Vault") (part "AC01000001001JA100"))
    )
    (comp (ref "R23")
      (value "1k")
      (footprint "RES_AC01_VIS")
      (description "VISHAY AC01000001001JA100 Through Hole Resistor, 1 kohm, Axial Leaded, 1 W, 5%, AC Series")
      (fields (field (name "TOLERANCE") "5%"))
      (libsource (lib "Altium Content Vault") (part "AC01000001001JA100"))
    )
    (comp (ref "R24")
      (value "1k")
      (footprint "RES_AC01_VIS")
      (description "VISHAY AC01000001001JA100 Through Hole Resistor, 1 kohm, Axial Leaded, 1 W, 5%, AC Series")
      (fields (field (name "TOLERANCE") "5%"))
      (libsource (lib "Altium Content Vault") (part "AC01000001001JA100"))
    )
    (comp (ref "R25")
      (value "AC01000001001JA100")
      (footprint "RES_AC01_VIS")
      (description "VISHAY AC01000001001JA100 Through Hole Resistor, 1 kohm, Axial Leaded, 1 W, 5%, AC Series")
      (fields (field (name "TOLERANCE") "5%"))
      (libsource (lib "") (part "AC01000001001JA100_1"))
    )
    (comp (ref "R26")
      (value "AC01000001001JA100")
      (footprint "RES_AC01_VIS")
      (description "VISHAY AC01000001001JA100 Through Hole Resistor, 1 kohm, Axial Leaded, 1 W, 5%, AC Series")
      (fields (field (name "TOLERANCE") "5%"))
      (libsource (lib "") (part "AC01000001001JA100_1"))
    )
    (comp (ref "R27")
      (value "AC01000001001JA100")
      (footprint "RES_AC01_VIS")
      (description "VISHAY AC01000001001JA100 Through Hole Resistor, 1 kohm, Axial Leaded, 1 W, 5%, AC Series")
      (fields (field (name "TOLERANCE") "5%"))
      (libsource (lib "") (part "AC01000001001JA100_1"))
    )
    (comp (ref "R28")
      (value "1k")
      (footprint "RES_AC01_VIS")
      (description "VISHAY AC01000001001JA100 Through Hole Resistor, 1 kohm, Axial Leaded, 1 W, 5%, AC Series")
      (fields (field (name "TOLERANCE") "5%"))
      (libsource (lib "Altium Content Vault") (part "AC01000001001JA100"))
    )
    (comp (ref "R29")
      (value "1k")
      (footprint "RES_AC01_VIS")
      (description "VISHAY AC01000001001JA100 Through Hole Resistor, 1 kohm, Axial Leaded, 1 W, 5%, AC Series")
      (fields (field (name "TOLERANCE") "5%"))
      (libsource (lib "Altium Content Vault") (part "AC01000001001JA100"))
    )
    (comp (ref "R30")
      (value "1k")
      (footprint "RES_AC01_VIS")
      (description "VISHAY AC01000001001JA100 Through Hole Resistor, 1 kohm, Axial Leaded, 1 W, 5%, AC Series")
      (fields (field (name "TOLERANCE") "5%"))
      (libsource (lib "Altium Content Vault") (part "AC01000001001JA100"))
    )
    (comp (ref "R31")
      (value "100K")
      (footprint "RES_AC01_VIS")
      (description "VISHAY AC01000001001JA100 Through Hole Resistor, 1 kohm, Axial Leaded, 1 W, 5%, AC Series")
      (fields (field (name "TOLERANCE") "5%"))
      (libsource (lib "Altium Content Vault") (part "AC01000001001JA100"))
    )
    (comp (ref "R32")
      (value "100K")
      (footprint "RES_AC01_VIS")
      (description "VISHAY AC01000001001JA100 Through Hole Resistor, 1 kohm, Axial Leaded, 1 W, 5%, AC Series")
      (fields (field (name "TOLERANCE") "5%"))
      (libsource (lib "Altium Content Vault") (part "AC01000001001JA100"))
    )
    (comp (ref "R33")
      (value "1k")
      (footprint "RES_AC01_VIS")
      (description "VISHAY AC01000001001JA100 Through Hole Resistor, 1 kohm, Axial Leaded, 1 W, 5%, AC Series")
      (fields (field (name "TOLERANCE") "5%"))
      (libsource (lib "Altium Content Vault") (part "AC01000001001JA100"))
    )
    (comp (ref "R34")
      (value "1k")
      (footprint "RES_AC01_VIS")
      (description "VISHAY AC01000001001JA100 Through Hole Resistor, 1 kohm, Axial Leaded, 1 W, 5%, AC Series")
      (fields (field (name "TOLERANCE") "5%"))
      (libsource (lib "Altium Content Vault") (part "AC01000001001JA100"))
    )
    (comp (ref "R35")
      (value "1k")
      (footprint "RES_AC01_VIS")
      (description "VISHAY AC01000001001JA100 Through Hole Resistor, 1 kohm, Axial Leaded, 1 W, 5%, AC Series")
      (fields (field (name "TOLERANCE") "5%"))
      (libsource (lib "Altium Content Vault") (part "AC01000001001JA100"))
    )
    (comp (ref "R36")
      (value "100K")
      (footprint "RES_AC01_VIS")
      (description "VISHAY AC01000001001JA100 Through Hole Resistor, 1 kohm, Axial Leaded, 1 W, 5%, AC Series")
      (fields (field (name "TOLERANCE") "5%"))
      (libsource (lib "Altium Content Vault") (part "AC01000001001JA100"))
    )
    (comp (ref "R37")
      (value "100K")
      (footprint "RES_AC01_VIS")
      (description "VISHAY AC01000001001JA100 Through Hole Resistor, 1 kohm, Axial Leaded, 1 W, 5%, AC Series")
      (fields (field (name "TOLERANCE") "5%"))
      (libsource (lib "Altium Content Vault") (part "AC01000001001JA100"))
    )
    (comp (ref "R38")
      (value "100K")
      (footprint "RES_AC01_VIS")
      (description "VISHAY AC01000001001JA100 Through Hole Resistor, 1 kohm, Axial Leaded, 1 W, 5%, AC Series")
      (fields (field (name "TOLERANCE") "5%"))
      (libsource (lib "Altium Content Vault") (part "AC01000001001JA100"))
    )
    (comp (ref "R39")
      (value "100K")
      (footprint "RES_AC01_VIS")
      (description "VISHAY AC01000001001JA100 Through Hole Resistor, 1 kohm, Axial Leaded, 1 W, 5%, AC Series")
      (fields (field (name "TOLERANCE") "5%"))
      (libsource (lib "Altium Content Vault") (part "AC01000001001JA100"))
    )
    (comp (ref "R40")
      (value "100K")
      (footprint "RES_AC01_VIS")
      (description "VISHAY AC01000001001JA100 Through Hole Resistor, 1 kohm, Axial Leaded, 1 W, 5%, AC Series")
      (fields (field (name "TOLERANCE") "5%"))
      (libsource (lib "Altium Content Vault") (part "AC01000001001JA100"))
    )
    (comp (ref "R41")
      (value "100K")
      (footprint "RES_AC01_VIS")
      (description "VISHAY AC01000001001JA100 Through Hole Resistor, 1 kohm, Axial Leaded, 1 W, 5%, AC Series")
      (fields (field (name "TOLERANCE") "5%"))
      (libsource (lib "Altium Content Vault") (part "AC01000001001JA100"))
    )
    (comp (ref "R42")
      (value "100K")
      (footprint "RES_AC01_VIS")
      (description "VISHAY AC01000001001JA100 Through Hole Resistor, 1 kohm, Axial Leaded, 1 W, 5%, AC Series")
      (fields (field (name "TOLERANCE") "5%"))
      (libsource (lib "Altium Content Vault") (part "AC01000001001JA100"))
    )
    (comp (ref "R43")
      (value "100K")
      (footprint "RES_AC01_VIS")
      (description "VISHAY AC01000001001JA100 Through Hole Resistor, 1 kohm, Axial Leaded, 1 W, 5%, AC Series")
      (fields (field (name "TOLERANCE") "5%"))
      (libsource (lib "Altium Content Vault") (part "AC01000001001JA100"))
    )
    (comp (ref "R44")
      (value "100K")
      (footprint "RES_AC01_VIS")
      (description "VISHAY AC01000001001JA100 Through Hole Resistor, 1 kohm, Axial Leaded, 1 W, 5%, AC Series")
      (fields (field (name "TOLERANCE") "5%"))
      (libsource (lib "Altium Content Vault") (part "AC01000001001JA100"))
    )
    (comp (ref "R45")
      (value "100K")
      (footprint "RES_AC01_VIS")
      (description "VISHAY AC01000001001JA100 Through Hole Resistor, 1 kohm, Axial Leaded, 1 W, 5%, AC Series")
      (fields (field (name "TOLERANCE") "5%"))
      (libsource (lib "Altium Content Vault") (part "AC01000001001JA100"))
    )
    (comp (ref "R46")
      (value "1k")
      (footprint "RES_AC01_VIS")
      (description "VISHAY AC01000001001JA100 Through Hole Resistor, 1 kohm, Axial Leaded, 1 W, 5%, AC Series")
      (fields (field (name "TOLERANCE") "5%"))
      (libsource (lib "Altium Content Vault") (part "AC01000001001JA100"))
    )
    (comp (ref "R47")
      (value "1k")
      (footprint "RES_AC01_VIS")
      (description "VISHAY AC01000001001JA100 Through Hole Resistor, 1 kohm, Axial Leaded, 1 W, 5%, AC Series")
      (fields (field (name "TOLERANCE") "5%"))
      (libsource (lib "") (part "AC01000001001JA100_1"))
    )
    (comp (ref "R48")
      (value "1k")
      (footprint "RES_AC01_VIS")
      (description "VISHAY AC01000001001JA100 Through Hole Resistor, 1 kohm, Axial Leaded, 1 W, 5%, AC Series")
      (fields (field (name "TOLERANCE") "5%"))
      (libsource (lib "") (part "AC01000001001JA100_1"))
    )
    (comp (ref "R49")
      (value "100K")
      (footprint "RES_AC01_VIS")
      (description "VISHAY AC01000001001JA100 Through Hole Resistor, 1 kohm, Axial Leaded, 1 W, 5%, AC Series")
      (fields (field (name "TOLERANCE") "5%"))
      (libsource (lib "Altium Content Vault") (part "AC01000001001JA100"))
    )
    (comp (ref "R50")
      (value "1k")
      (footprint "RES_AC01_VIS")
      (description "VISHAY AC01000001001JA100 Through Hole Resistor, 1 kohm, Axial Leaded, 1 W, 5%, AC Series")
      (fields (field (name "TOLERANCE") "5%"))
      (libsource (lib "") (part "AC01000001001JA100_1"))
    )
    (comp (ref "R51")
      (value "1k")
      (footprint "RES_AC01_VIS")
      (description "VISHAY AC01000001001JA100 Through Hole Resistor, 1 kohm, Axial Leaded, 1 W, 5%, AC Series")
      (fields (field (name "TOLERANCE") "5%"))
      (libsource (lib "Altium Content Vault") (part "AC01000001001JA100"))
    )
    (comp (ref "R52")
      (value "100K")
      (footprint "RES_AC01_VIS")
      (description "VISHAY AC01000001001JA100 Through Hole Resistor, 1 kohm, Axial Leaded, 1 W, 5%, AC Series")
      (fields (field (name "TOLERANCE") "5%"))
      (libsource (lib "Altium Content Vault") (part "AC01000001001JA100"))
    )
    (comp (ref "R53")
      (value "1k")
      (footprint "RES_AC01_VIS")
      (description "VISHAY AC01000001001JA100 Through Hole Resistor, 1 kohm, Axial Leaded, 1 W, 5%, AC Series")
      (fields (field (name "TOLERANCE") "5%"))
      (libsource (lib "Altium Content Vault") (part "AC01000001001JA100"))
    )
    (comp (ref "R54")
      (value "1k")
      (footprint "RES_AC01_VIS")
      (description "VISHAY AC01000001001JA100 Through Hole Resistor, 1 kohm, Axial Leaded, 1 W, 5%, AC Series")
      (fields (field (name "TOLERANCE") "5%"))
      (libsource (lib "Altium Content Vault") (part "AC01000001001JA100"))
    )
    (comp (ref "R55")
      (value "1k")
      (footprint "RES_AC01_VIS")
      (description "VISHAY AC01000001001JA100 Through Hole Resistor, 1 kohm, Axial Leaded, 1 W, 5%, AC Series")
      (fields (field (name "TOLERANCE") "5%"))
      (libsource (lib "") (part "AC01000001001JA100_1"))
    )
    (comp (ref "R56")
      (value "1k")
      (footprint "RES_AC01_VIS")
      (description "VISHAY AC01000001001JA100 Through Hole Resistor, 1 kohm, Axial Leaded, 1 W, 5%, AC Series")
      (fields (field (name "TOLERANCE") "5%"))
      (libsource (lib "") (part "AC01000001001JA100_1"))
    )
    (comp (ref "R57")
      (value "1k")
      (footprint "RES_AC01_VIS")
      (description "VISHAY AC01000001001JA100 Through Hole Resistor, 1 kohm, Axial Leaded, 1 W, 5%, AC Series")
      (fields (field (name "TOLERANCE") "5%"))
      (libsource (lib "") (part "AC01000001001JA100_1"))
    )
    (comp (ref "R58")
      (value "1k")
      (footprint "RES_AC01_VIS")
      (description "VISHAY AC01000001001JA100 Through Hole Resistor, 1 kohm, Axial Leaded, 1 W, 5%, AC Series")
      (fields (field (name "TOLERANCE") "5%"))
      (libsource (lib "Altium Content Vault") (part "AC01000001001JA100"))
    )
    (comp (ref "R59")
      (value "1k")
      (footprint "RES_AC01_VIS")
      (description "VISHAY AC01000001001JA100 Through Hole Resistor, 1 kohm, Axial Leaded, 1 W, 5%, AC Series")
      (fields (field (name "TOLERANCE") "5%"))
      (libsource (lib "Altium Content Vault") (part "AC01000001001JA100"))
    )
    (comp (ref "R60")
      (value "100K")
      (footprint "RES_AC01_VIS")
      (description "VISHAY AC01000001001JA100 Through Hole Resistor, 1 kohm, Axial Leaded, 1 W, 5%, AC Series")
      (fields (field (name "TOLERANCE") "5%"))
      (libsource (lib "Altium Content Vault") (part "AC01000001001JA100"))
    )
    (comp (ref "R61")
      (value "1k")
      (footprint "RES_AC01_VIS")
      (description "VISHAY AC01000001001JA100 Through Hole Resistor, 1 kohm, Axial Leaded, 1 W, 5%, AC Series")
      (fields (field (name "TOLERANCE") "5%"))
      (libsource (lib "Altium Content Vault") (part "AC01000001001JA100"))
    )
    (comp (ref "R62")
      (value "1k")
      (footprint "RES_AC01_VIS")
      (description "VISHAY AC01000001001JA100 Through Hole Resistor, 1 kohm, Axial Leaded, 1 W, 5%, AC Series")
      (fields (field (name "TOLERANCE") "5%"))
      (libsource (lib "") (part "AC01000001001JA100_1"))
    )
    (comp (ref "R63")
      (value "1k")
      (footprint "RES_AC01_VIS")
      (description "VISHAY AC01000001001JA100 Through Hole Resistor, 1 kohm, Axial Leaded, 1 W, 5%, AC Series")
      (fields (field (name "TOLERANCE") "5%"))
      (libsource (lib "Altium Content Vault") (part "AC01000001001JA100"))
    )
    (comp (ref "U1")
      (value "LM2596SX-ADJ/NOPB")
      (footprint "KTT0005B_L")
      (fields (field (name "PARTNUMBER") "LM2596") (field (name "MANUFACTURER") "Texas Instruments"))
      (libsource (lib "Altium Content Vault") (part "TI-LM2596-TO-263-5"))
    )
    (comp (ref "X1")
      (value "571-3-282836-3")
      (footprint "PCB3:PCBComponent_1")
      (libsource (lib "Relay Aram") (part "Connector"))
    )
    (comp (ref "X2")
      (value "571-3-282836-3")
      (footprint "PCB3:PCBComponent_1")
      (libsource (lib "Relay Aram") (part "Connector"))
    )
    (comp (ref "X3")
      (value "571-3-282836-3")
      (footprint "PCB3:PCBComponent_1")
      (libsource (lib "Relay Aram") (part "Connector"))
    )
    (comp (ref "X4")
      (value "571-3-282836-3")
      (footprint "PCB3:PCBComponent_1")
      (libsource (lib "Relay Aram") (part "Connector"))
    )
  )
  (nets
    (net (code "1") (name "+24V") (class "Default")
      (node (ref "C1") (pin "2") (pinfunction "A_2") (pintype "passive"))
      (node (ref "C3") (pin "1") (pinfunction "1_1") (pintype "passive"))
      (node (ref "D1") (pin "1") (pinfunction "C_1") (pintype "passive"))
      (node (ref "D10") (pin "2") (pinfunction "A_2") (pintype "passive"))
      (node (ref "D11") (pin "1") (pinfunction "C_1") (pintype "passive"))
      (node (ref "D12") (pin "2") (pinfunction "A_2") (pintype "passive"))
      (node (ref "D13") (pin "1") (pinfunction "C_1") (pintype "passive"))
      (node (ref "D14") (pin "2") (pinfunction "A_2") (pintype "passive"))
      (node (ref "D15") (pin "1") (pinfunction "C_1") (pintype "passive"))
      (node (ref "D16") (pin "2") (pinfunction "A_2") (pintype "passive"))
      (node (ref "D17") (pin "1") (pinfunction "C_1") (pintype "passive"))
      (node (ref "D18") (pin "2") (pinfunction "A_2") (pintype "passive"))
      (node (ref "D19") (pin "1") (pinfunction "C_1") (pintype "passive"))
      (node (ref "D2") (pin "2") (pinfunction "A_2") (pintype "passive"))
      (node (ref "D20") (pin "2") (pinfunction "A_2") (pintype "passive"))
      (node (ref "D21") (pin "1") (pinfunction "C_1") (pintype "passive"))
      (node (ref "D22") (pin "2") (pinfunction "A_2") (pintype "passive"))
      (node (ref "D23") (pin "1") (pinfunction "C_1") (pintype "passive"))
      (node (ref "D24") (pin "2") (pinfunction "A_2") (pintype "passive"))
      (node (ref "D3") (pin "1") (pinfunction "C_1") (pintype "passive"))
      (node (ref "D31") (pin "1") (pinfunction "C_1") (pintype "passive"))
      (node (ref "D32") (pin "2") (pinfunction "A_2") (pintype "passive"))
      (node (ref "D33") (pin "1") (pinfunction "C_1") (pintype "passive"))
      (node (ref "D34") (pin "2") (pinfunction "A_2") (pintype "passive"))
      (node (ref "D35") (pin "1") (pinfunction "C_1") (pintype "passive"))
      (node (ref "D36") (pin "2") (pinfunction "A_2") (pintype "passive"))
      (node (ref "D4") (pin "2") (pinfunction "A_2") (pintype "passive"))
      (node (ref "D5") (pin "1") (pinfunction "C_1") (pintype "passive"))
      (node (ref "D6") (pin "2") (pinfunction "A_2") (pintype "passive"))
      (node (ref "D7") (pin "1") (pinfunction "C_1") (pintype "passive"))
      (node (ref "D8") (pin "2") (pinfunction "A_2") (pintype "passive"))
      (node (ref "D9") (pin "1") (pinfunction "C_1") (pintype "passive"))
      (node (ref "K1") (pin "5") (pinfunction "COIL_2_5") (pintype "passive"))
      (node (ref "K10") (pin "5") (pinfunction "COIL_2_5") (pintype "passive"))
      (node (ref "K11") (pin "5") (pinfunction "COIL_2_5") (pintype "passive"))
      (node (ref "K12") (pin "5") (pinfunction "COIL_2_5") (pintype "passive"))
      (node (ref "K13") (pin "5") (pinfunction "COIL_2_5") (pintype "passive"))
      (node (ref "K14") (pin "5") (pinfunction "COIL_2_5") (pintype "passive"))
      (node (ref "K15") (pin "5") (pinfunction "COIL_2_5") (pintype "passive"))
      (node (ref "K2") (pin "5") (pinfunction "COIL_2_5") (pintype "passive"))
      (node (ref "K3") (pin "5") (pinfunction "COIL_2_5") (pintype "passive"))
      (node (ref "K4") (pin "5") (pinfunction "COIL_2_5") (pintype "passive"))
      (node (ref "K5") (pin "5") (pinfunction "COIL_2_5") (pintype "passive"))
      (node (ref "K6") (pin "5") (pinfunction "COIL_2_5") (pintype "passive"))
      (node (ref "K7") (pin "5") (pinfunction "COIL_2_5") (pintype "passive"))
      (node (ref "K8") (pin "5") (pinfunction "COIL_2_5") (pintype "passive"))
      (node (ref "K9") (pin "5") (pinfunction "COIL_2_5") (pintype "passive"))
      (node (ref "L1") (pin "2") (pinfunction "2_2") (pintype "passive"))
      (node (ref "R25") (pin "1") (pinfunction "1_1") (pintype "passive"))
      (node (ref "R26") (pin "1") (pinfunction "1_1") (pintype "passive"))
      (node (ref "R31") (pin "2") (pinfunction "2_2") (pintype "passive"))
      (node (ref "R32") (pin "2") (pinfunction "2_2") (pintype "passive"))
      (node (ref "R36") (pin "2") (pinfunction "2_2") (pintype "passive"))
      (node (ref "R37") (pin "2") (pinfunction "2_2") (pintype "passive"))
      (node (ref "R38") (pin "2") (pinfunction "2_2") (pintype "passive"))
      (node (ref "R39") (pin "2") (pinfunction "2_2") (pintype "passive"))
      (node (ref "R40") (pin "2") (pinfunction "2_2") (pintype "passive"))
      (node (ref "R41") (pin "2") (pinfunction "2_2") (pintype "passive"))
      (node (ref "R42") (pin "2") (pinfunction "2_2") (pintype "passive"))
      (node (ref "R43") (pin "2") (pinfunction "2_2") (pintype "passive"))
      (node (ref "R44") (pin "2") (pinfunction "2_2") (pintype "passive"))
      (node (ref "R45") (pin "2") (pinfunction "2_2") (pintype "passive"))
      (node (ref "R49") (pin "2") (pinfunction "2_2") (pintype "passive"))
      (node (ref "R52") (pin "2") (pinfunction "2_2") (pintype "passive"))
      (node (ref "R60") (pin "2") (pinfunction "2_2") (pintype "passive"))
      (node (ref "X4") (pin "1") (pinfunction "1_1") (pintype "passive"))
      (node (ref "X4") (pin "2") (pinfunction "2_2") (pintype "passive"))
    )
    (net (code "2") (name "/IN_1") (class "Default")
      (node (ref "J1") (pin "15") (pinfunction "15_15") (pintype "passive"))
      (node (ref "R28") (pin "1") (pinfunction "1_1") (pintype "passive"))
    )
    (net (code "3") (name "/IN_2") (class "Default")
      (node (ref "J1") (pin "14") (pinfunction "14_14") (pintype "passive"))
      (node (ref "R2") (pin "1") (pinfunction "1_1") (pintype "passive"))
    )
    (net (code "4") (name "/IN_3") (class "Default")
      (node (ref "J1") (pin "13") (pinfunction "13_13") (pintype "passive"))
      (node (ref "R30") (pin "1") (pinfunction "1_1") (pintype "passive"))
    )
    (net (code "5") (name "/IN_4") (class "Default")
      (node (ref "J1") (pin "12") (pinfunction "12_12") (pintype "passive"))
      (node (ref "R33") (pin "1") (pinfunction "1_1") (pintype "passive"))
    )
    (net (code "6") (name "/IN_5") (class "Default")
      (node (ref "J1") (pin "11") (pinfunction "11_11") (pintype "passive"))
      (node (ref "R34") (pin "1") (pinfunction "1_1") (pintype "passive"))
    )
    (net (code "7") (name "/IN_6") (class "Default")
      (node (ref "J1") (pin "10") (pinfunction "10_10") (pintype "passive"))
      (node (ref "R35") (pin "1") (pinfunction "1_1") (pintype "passive"))
    )
    (net (code "8") (name "/IN_7") (class "Default")
      (node (ref "J1") (pin "9") (pinfunction "9_9") (pintype "passive"))
      (node (ref "R46") (pin "1") (pinfunction "1_1") (pintype "passive"))
    )
    (net (code "9") (name "/IN_8") (class "Default")
      (node (ref "J1") (pin "8") (pinfunction "8_8") (pintype "passive"))
      (node (ref "R51") (pin "1") (pinfunction "1_1") (pintype "passive"))
    )
    (net (code "10") (name "/IN_9") (class "Default")
      (node (ref "J1") (pin "7") (pinfunction "7_7") (pintype "passive"))
      (node (ref "R15") (pin "1") (pinfunction "1_1") (pintype "passive"))
    )
    (net (code "11") (name "/IN_10") (class "Default")
      (node (ref "J1") (pin "6") (pinfunction "6_6") (pintype "passive"))
      (node (ref "R16") (pin "1") (pinfunction "1_1") (pintype "passive"))
    )
    (net (code "12") (name "/IN_11") (class "Default")
      (node (ref "J1") (pin "5") (pinfunction "5_5") (pintype "passive"))
      (node (ref "R17") (pin "1") (pinfunction "1_1") (pintype "passive"))
    )
    (net (code "13") (name "/IN_12") (class "Default")
      (node (ref "J1") (pin "4") (pinfunction "4_4") (pintype "passive"))
      (node (ref "R18") (pin "1") (pinfunction "1_1") (pintype "passive"))
    )
    (net (code "14") (name "/IN_13") (class "Default")
      (node (ref "J1") (pin "3") (pinfunction "3_3") (pintype "passive"))
      (node (ref "R53") (pin "1") (pinfunction "1_1") (pintype "passive"))
    )
    (net (code "15") (name "/IN_14") (class "Default")
      (node (ref "J1") (pin "2") (pinfunction "2_2") (pintype "passive"))
      (node (ref "R54") (pin "1") (pinfunction "1_1") (pintype "passive"))
    )
    (net (code "16") (name "/IN_15") (class "Default")
      (node (ref "J1") (pin "1") (pinfunction "1_1") (pintype "passive"))
      (node (ref "R61") (pin "1") (pinfunction "1_1") (pintype "passive"))
    )
    (net (code "17") (name "/OUT_1") (class "Default")
      (node (ref "K1") (pin "4") (pinfunction "NC_4") (pintype "passive"))
      (node (ref "X3") (pin "5") (pinfunction "5_5") (pintype "passive"))
    )
    (net (code "18") (name "/OUT_2") (class "Default")
      (node (ref "K2") (pin "4") (pinfunction "NC_4") (pintype "passive"))
      (node (ref "X3") (pin "4") (pinfunction "4_4") (pintype "passive"))
    )
    (net (code "19") (name "/OUT_3") (class "Default")
      (node (ref "K3") (pin "4") (pinfunction "NC_4") (pintype "passive"))
      (node (ref "X3") (pin "3") (pinfunction "3_3") (pintype "passive"))
    )
    (net (code "20") (name "/OUT_4") (class "Default")
      (node (ref "K4") (pin "4") (pinfunction "NC_4") (pintype "passive"))
      (node (ref "X3") (pin "2") (pinfunction "2_2") (pintype "passive"))
    )
    (net (code "21") (name "/OUT_5") (class "Default")
      (node (ref "K5") (pin "4") (pinfunction "NC_4") (pintype "passive"))
      (node (ref "X3") (pin "1") (pinfunction "1_1") (pintype "passive"))
    )
    (net (code "22") (name "/OUT_6") (class "Default")
      (node (ref "K6") (pin "4") (pinfunction "NC_4") (pintype "passive"))
      (node (ref "X2") (pin "5") (pinfunction "5_5") (pintype "passive"))
    )
    (net (code "23") (name "/OUT_7") (class "Default")
      (node (ref "K7") (pin "4") (pinfunction "NC_4") (pintype "passive"))
      (node (ref "X2") (pin "4") (pinfunction "4_4") (pintype "passive"))
    )
    (net (code "24") (name "/OUT_8") (class "Default")
      (node (ref "K8") (pin "4") (pinfunction "NC_4") (pintype "passive"))
      (node (ref "X2") (pin "3") (pinfunction "3_3") (pintype "passive"))
    )
    (net (code "25") (name "/OUT_9") (class "Default")
      (node (ref "K9") (pin "4") (pinfunction "NC_4") (pintype "passive"))
      (node (ref "X2") (pin "2") (pinfunction "2_2") (pintype "passive"))
    )
    (net (code "26") (name "/OUT_10") (class "Default")
      (node (ref "K10") (pin "4") (pinfunction "NC_4") (pintype "passive"))
      (node (ref "X2") (pin "1") (pinfunction "1_1") (pintype "passive"))
    )
    (net (code "27") (name "/OUT_11") (class "Default")
      (node (ref "K11") (pin "4") (pinfunction "NC_4") (pintype "passive"))
      (node (ref "X1") (pin "5") (pinfunction "5_5") (pintype "passive"))
    )
    (net (code "28") (name "/OUT_12") (class "Default")
      (node (ref "K12") (pin "4") (pinfunction "NC_4") (pintype "passive"))
      (node (ref "X1") (pin "4") (pinfunction "4_4") (pintype "passive"))
    )
    (net (code "29") (name "/OUT_13") (class "Default")
      (node (ref "K13") (pin "4") (pinfunction "NC_4") (pintype "passive"))
      (node (ref "X1") (pin "3") (pinfunction "3_3") (pintype "passive"))
    )
    (net (code "30") (name "/OUT_14") (class "Default")
      (node (ref "K14") (pin "4") (pinfunction "NC_4") (pintype "passive"))
      (node (ref "X1") (pin "2") (pinfunction "2_2") (pintype "passive"))
    )
    (net (code "31") (name "/OUT_15") (class "Default")
      (node (ref "K15") (pin "4") (pinfunction "NC_4") (pintype "passive"))
      (node (ref "X1") (pin "1") (pinfunction "1_1") (pintype "passive"))
    )
    (net (code "32") (name "GND") (class "Default")
      (node (ref "C1") (pin "1") (pinfunction "C_1") (pintype "passive"))
      (node (ref "C2") (pin "2") (pinfunction "2_2") (pintype "passive"))
      (node (ref "C3") (pin "2") (pinfunction "2_2") (pintype "passive"))
      (node (ref "C4") (pin "1") (pinfunction "C_1") (pintype "passive"))
      (node (ref "D25") (pin "2") (pinfunction "A_2") (pintype "passive"))
      (node (ref "D27") (pin "1") (pinfunction "C_1") (pintype "passive"))
      (node (ref "D28") (pin "2") (pinfunction "A_2") (pintype "passive"))
      (node (ref "D29") (pin "1") (pinfunction "K_1") (pintype "passive"))
      (node (ref "OP1") (pin "3") (pinfunction "E_3") (pintype "passive"))
      (node (ref "OP10") (pin "3") (pinfunction "E_3") (pintype "passive"))
      (node (ref "OP11") (pin "3") (pinfunction "E_3") (pintype "passive"))
      (node (ref "OP12") (pin "3") (pinfunction "E_3") (pintype "passive"))
      (node (ref "OP13") (pin "3") (pinfunction "E_3") (pintype "passive"))
      (node (ref "OP14") (pin "3") (pinfunction "E_3") (pintype "passive"))
      (node (ref "OP15") (pin "3") (pinfunction "E_3") (pintype "passive"))
      (node (ref "OP2") (pin "3") (pinfunction "E_3") (pintype "passive"))
      (node (ref "OP3") (pin "3") (pinfunction "E_3") (pintype "passive"))
      (node (ref "OP4") (pin "3") (pinfunction "E_3") (pintype "passive"))
      (node (ref "OP5") (pin "3") (pinfunction "E_3") (pintype "passive"))
      (node (ref "OP6") (pin "3") (pinfunction "E_3") (pintype "passive"))
      (node (ref "OP7") (pin "3") (pinfunction "E_3") (pintype "passive"))
      (node (ref "OP8") (pin "3") (pinfunction "E_3") (pintype "passive"))
      (node (ref "OP9") (pin "3") (pinfunction "E_3") (pintype "passive"))
      (node (ref "Q1") (pin "2") (pinfunction "C_2") (pintype "passive"))
      (node (ref "Q10") (pin "2") (pinfunction "C_2") (pintype "passive"))
      (node (ref "Q11") (pin "2") (pinfunction "C_2") (pintype "passive"))
      (node (ref "Q12") (pin "2") (pinfunction "C_2") (pintype "passive"))
      (node (ref "Q13") (pin "2") (pinfunction "C_2") (pintype "passive"))
      (node (ref "Q14") (pin "2") (pinfunction "C_2") (pintype "passive"))
      (node (ref "Q15") (pin "2") (pinfunction "C_2") (pintype "passive"))
      (node (ref "Q2") (pin "2") (pinfunction "C_2") (pintype "passive"))
      (node (ref "Q3") (pin "2") (pinfunction "C_2") (pintype "passive"))
      (node (ref "Q4") (pin "2") (pinfunction "C_2") (pintype "passive"))
      (node (ref "Q5") (pin "2") (pinfunction "C_2") (pintype "passive"))
      (node (ref "Q6") (pin "2") (pinfunction "C_2") (pintype "passive"))
      (node (ref "Q7") (pin "2") (pinfunction "C_2") (pintype "passive"))
      (node (ref "Q8") (pin "2") (pinfunction "C_2") (pintype "passive"))
      (node (ref "Q9") (pin "2") (pinfunction "C_2") (pintype "passive"))
      (node (ref "R27") (pin "2") (pinfunction "2_2") (pintype "passive"))
      (node (ref "U1") (pin "3") (pinfunction "GND_3") (pintype "power_in"))
      (node (ref "U1") (pin "5") (pinfunction "~{ON}/OFF_5") (pintype "input"))
      (node (ref "U1") (pin "6") (pinfunction "GND_6") (pintype "power_in"))
      (node (ref "X4") (pin "3") (pinfunction "3_3") (pintype "passive"))
    )
    (net (code "33") (name "GND2") (class "Default")
      (node (ref "J1") (pin "16") (pinfunction "16_16") (pintype "passive"))
      (node (ref "J1") (pin "17") (pinfunction "17_17") (pintype "passive"))
      (node (ref "J1") (pin "18") (pinfunction "18_18") (pintype "passive"))
      (node (ref "J1") (pin "19") (pinfunction "19_19") (pintype "passive"))
      (node (ref "J1") (pin "20") (pinfunction "20_20") (pintype "passive"))
      (node (ref "OP1") (pin "2") (pinfunction "C_2") (pintype "passive"))
      (node (ref "OP10") (pin "2") (pinfunction "C_2") (pintype "passive"))
      (node (ref "OP11") (pin "2") (pinfunction "C_2") (pintype "passive"))
      (node (ref "OP12") (pin "2") (pinfunction "C_2") (pintype "passive"))
      (node (ref "OP13") (pin "2") (pinfunction "C_2") (pintype "passive"))
      (node (ref "OP14") (pin "2") (pinfunction "C_2") (pintype "passive"))
      (node (ref "OP15") (pin "2") (pinfunction "C_2") (pintype "passive"))
      (node (ref "OP2") (pin "2") (pinfunction "C_2") (pintype "passive"))
      (node (ref "OP3") (pin "2") (pinfunction "C_2") (pintype "passive"))
      (node (ref "OP4") (pin "2") (pinfunction "C_2") (pintype "passive"))
      (node (ref "OP5") (pin "2") (pinfunction "C_2") (pintype "passive"))
      (node (ref "OP6") (pin "2") (pinfunction "C_2") (pintype "passive"))
      (node (ref "OP7") (pin "2") (pinfunction "C_2") (pintype "passive"))
      (node (ref "OP8") (pin "2") (pinfunction "C_2") (pintype "passive"))
      (node (ref "OP9") (pin "2") (pinfunction "C_2") (pintype "passive"))
    )
    (net (code "34") (name "L") (class "Default")
      (node (ref "J2") (pin "1") (pinfunction "1_1") (pintype "passive"))
      (node (ref "J2") (pin "2") (pinfunction "2_2") (pintype "passive"))
      (node (ref "K1") (pin "1") (pinfunction "COM_1") (pintype "passive"))
      (node (ref "K10") (pin "1") (pinfunction "COM_1") (pintype "passive"))
      (node (ref "K11") (pin "1") (pinfunction "COM_1") (pintype "passive"))
      (node (ref "K12") (pin "1") (pinfunction "COM_1") (pintype "passive"))
      (node (ref "K13") (pin "1") (pinfunction "COM_1") (pintype "passive"))
      (node (ref "K14") (pin "1") (pinfunction "COM_1") (pintype "passive"))
      (node (ref "K15") (pin "1") (pinfunction "COM_1") (pintype "passive"))
      (node (ref "K2") (pin "1") (pinfunction "COM_1") (pintype "passive"))
      (node (ref "K3") (pin "1") (pinfunction "COM_1") (pintype "passive"))
      (node (ref "K4") (pin "1") (pinfunction "COM_1") (pintype "passive"))
      (node (ref "K5") (pin "1") (pinfunction "COM_1") (pintype "passive"))
      (node (ref "K6") (pin "1") (pinfunction "COM_1") (pintype "passive"))
      (node (ref "K7") (pin "1") (pinfunction "COM_1") (pintype "passive"))
      (node (ref "K8") (pin "1") (pinfunction "COM_1") (pintype "passive"))
      (node (ref "K9") (pin "1") (pinfunction "COM_1") (pintype "passive"))
    )
    (net (code "35") (name "Net-(C4-A)") (class "Default")
      (node (ref "C2") (pin "1") (pinfunction "1_1") (pintype "passive"))
      (node (ref "C4") (pin "2") (pinfunction "A_2") (pintype "passive"))
      (node (ref "D26") (pin "2") (pinfunction "A_2") (pintype "passive"))
      (node (ref "D30") (pin "1") (pinfunction "K_1") (pintype "passive"))
      (node (ref "U1") (pin "1") (pinfunction "+VIN_1") (pintype "power_in"))
    )
    (net (code "36") (name "Net-(D1-A)") (class "Default")
      (node (ref "D1") (pin "2") (pinfunction "A_2") (pintype "passive"))
      (node (ref "K1") (pin "2") (pinfunction "COIL_1_2") (pintype "passive"))
      (node (ref "Q1") (pin "1") (pinfunction "E_1") (pintype "passive"))
      (node (ref "R7") (pin "2") (pinfunction "2_2") (pintype "passive"))
    )
    (net (code "37") (name "Net-(D2-C)") (class "Default")
      (node (ref "D2") (pin "1") (pinfunction "C_1") (pintype "passive"))
      (node (ref "R7") (pin "1") (pinfunction "1_1") (pintype "passive"))
    )
    (net (code "38") (name "Net-(D3-A)") (class "Default")
      (node (ref "D3") (pin "2") (pinfunction "A_2") (pintype "passive"))
      (node (ref "K2") (pin "2") (pinfunction "COIL_1_2") (pintype "passive"))
      (node (ref "Q2") (pin "1") (pinfunction "E_1") (pintype "passive"))
      (node (ref "R8") (pin "2") (pinfunction "2_2") (pintype "passive"))
    )
    (net (code "39") (name "Net-(D4-C)") (class "Default")
      (node (ref "D4") (pin "1") (pinfunction "C_1") (pintype "passive"))
      (node (ref "R8") (pin "1") (pinfunction "1_1") (pintype "passive"))
    )
    (net (code "40") (name "Net-(D5-A)") (class "Default")
      (node (ref "D5") (pin "2") (pinfunction "A_2") (pintype "passive"))
      (node (ref "K3") (pin "2") (pinfunction "COIL_1_2") (pintype "passive"))
      (node (ref "Q3") (pin "1") (pinfunction "E_1") (pintype "passive"))
      (node (ref "R9") (pin "2") (pinfunction "2_2") (pintype "passive"))
    )
    (net (code "41") (name "Net-(D6-C)") (class "Default")
      (node (ref "D6") (pin "1") (pinfunction "C_1") (pintype "passive"))
      (node (ref "R9") (pin "1") (pinfunction "1_1") (pintype "passive"))
    )
    (net (code "42") (name "Net-(D7-A)") (class "Default")
      (node (ref "D7") (pin "2") (pinfunction "A_2") (pintype "passive"))
      (node (ref "K4") (pin "2") (pinfunction "COIL_1_2") (pintype "passive"))
      (node (ref "Q4") (pin "1") (pinfunction "E_1") (pintype "passive"))
      (node (ref "R29") (pin "2") (pinfunction "2_2") (pintype "passive"))
    )
    (net (code "43") (name "Net-(D8-C)") (class "Default")
      (node (ref "D8") (pin "1") (pinfunction "C_1") (pintype "passive"))
      (node (ref "R29") (pin "1") (pinfunction "1_1") (pintype "passive"))
    )
    (net (code "44") (name "Net-(D9-A)") (class "Default")
      (node (ref "D9") (pin "2") (pinfunction "A_2") (pintype "passive"))
      (node (ref "K5") (pin "2") (pinfunction "COIL_1_2") (pintype "passive"))
      (node (ref "Q5") (pin "1") (pinfunction "E_1") (pintype "passive"))
      (node (ref "R11") (pin "2") (pinfunction "2_2") (pintype "passive"))
    )
    (net (code "45") (name "Net-(D10-C)") (class "Default")
      (node (ref "D10") (pin "1") (pinfunction "C_1") (pintype "passive"))
      (node (ref "R11") (pin "1") (pinfunction "1_1") (pintype "passive"))
    )
    (net (code "46") (name "Net-(D11-A)") (class "Default")
      (node (ref "D11") (pin "2") (pinfunction "A_2") (pintype "passive"))
      (node (ref "K6") (pin "2") (pinfunction "COIL_1_2") (pintype "passive"))
      (node (ref "Q6") (pin "1") (pinfunction "E_1") (pintype "passive"))
      (node (ref "R12") (pin "2") (pinfunction "2_2") (pintype "passive"))
    )
    (net (code "47") (name "Net-(D12-C)") (class "Default")
      (node (ref "D12") (pin "1") (pinfunction "C_1") (pintype "passive"))
      (node (ref "R12") (pin "1") (pinfunction "1_1") (pintype "passive"))
    )
    (net (code "48") (name "Net-(D13-A)") (class "Default")
      (node (ref "D13") (pin "2") (pinfunction "A_2") (pintype "passive"))
      (node (ref "K7") (pin "2") (pinfunction "COIL_1_2") (pintype "passive"))
      (node (ref "Q7") (pin "1") (pinfunction "E_1") (pintype "passive"))
      (node (ref "R19") (pin "2") (pinfunction "2_2") (pintype "passive"))
    )
    (net (code "49") (name "Net-(D14-C)") (class "Default")
      (node (ref "D14") (pin "1") (pinfunction "C_1") (pintype "passive"))
      (node (ref "R19") (pin "1") (pinfunction "1_1") (pintype "passive"))
    )
    (net (code "50") (name "Net-(D15-A)") (class "Default")
      (node (ref "D15") (pin "2") (pinfunction "A_2") (pintype "passive"))
      (node (ref "K8") (pin "2") (pinfunction "COIL_1_2") (pintype "passive"))
      (node (ref "Q8") (pin "1") (pinfunction "E_1") (pintype "passive"))
      (node (ref "R20") (pin "2") (pinfunction "2_2") (pintype "passive"))
    )
    (net (code "51") (name "Net-(D16-C)") (class "Default")
      (node (ref "D16") (pin "1") (pinfunction "C_1") (pintype "passive"))
      (node (ref "R20") (pin "1") (pinfunction "1_1") (pintype "passive"))
    )
    (net (code "52") (name "Net-(D17-A)") (class "Default")
      (node (ref "D17") (pin "2") (pinfunction "A_2") (pintype "passive"))
      (node (ref "K9") (pin "2") (pinfunction "COIL_1_2") (pintype "passive"))
      (node (ref "Q9") (pin "1") (pinfunction "E_1") (pintype "passive"))
      (node (ref "R21") (pin "2") (pinfunction "2_2") (pintype "passive"))
    )
    (net (code "53") (name "Net-(D18-C)") (class "Default")
      (node (ref "D18") (pin "1") (pinfunction "C_1") (pintype "passive"))
      (node (ref "R21") (pin "1") (pinfunction "1_1") (pintype "passive"))
    )
    (net (code "54") (name "Net-(D19-A)") (class "Default")
      (node (ref "D19") (pin "2") (pinfunction "A_2") (pintype "passive"))
      (node (ref "K10") (pin "2") (pinfunction "COIL_1_2") (pintype "passive"))
      (node (ref "Q10") (pin "1") (pinfunction "E_1") (pintype "passive"))
      (node (ref "R22") (pin "2") (pinfunction "2_2") (pintype "passive"))
    )
    (net (code "55") (name "Net-(D20-C)") (class "Default")
      (node (ref "D20") (pin "1") (pinfunction "C_1") (pintype "passive"))
      (node (ref "R22") (pin "1") (pinfunction "1_1") (pintype "passive"))
    )
    (net (code "56") (name "Net-(D21-A)") (class "Default")
      (node (ref "D21") (pin "2") (pinfunction "A_2") (pintype "passive"))
      (node (ref "K11") (pin "2") (pinfunction "COIL_1_2") (pintype "passive"))
      (node (ref "Q11") (pin "1") (pinfunction "E_1") (pintype "passive"))
      (node (ref "R23") (pin "2") (pinfunction "2_2") (pintype "passive"))
    )
    (net (code "57") (name "Net-(D22-C)") (class "Default")
      (node (ref "D22") (pin "1") (pinfunction "C_1") (pintype "passive"))
      (node (ref "R23") (pin "1") (pinfunction "1_1") (pintype "passive"))
    )
    (net (code "58") (name "Net-(D23-A)") (class "Default")
      (node (ref "D23") (pin "2") (pinfunction "A_2") (pintype "passive"))
      (node (ref "K12") (pin "2") (pinfunction "COIL_1_2") (pintype "passive"))
      (node (ref "Q12") (pin "1") (pinfunction "E_1") (pintype "passive"))
      (node (ref "R24") (pin "2") (pinfunction "2_2") (pintype "passive"))
    )
    (net (code "59") (name "Net-(D24-C)") (class "Default")
      (node (ref "D24") (pin "1") (pinfunction "C_1") (pintype "passive"))
      (node (ref "R24") (pin "1") (pinfunction "1_1") (pintype "passive"))
    )
    (net (code "60") (name "Net-(D27-A)") (class "Default")
      (node (ref "D27") (pin "2") (pinfunction "A_2") (pintype "passive"))
      (node (ref "R26") (pin "2") (pinfunction "2_2") (pintype "passive"))
    )
    (net (code "61") (name "Net-(D28-C)") (class "Default")
      (node (ref "D28") (pin "1") (pinfunction "C_1") (pintype "passive"))
      (node (ref "L1") (pin "1") (pinfunction "1_1") (pintype "passive"))
      (node (ref "U1") (pin "2") (pinfunction "OUT_2") (pintype "power_in"))
    )
    (net (code "62") (name "Net-(D31-A)") (class "Default")
      (node (ref "D31") (pin "2") (pinfunction "A_2") (pintype "passive"))
      (node (ref "K13") (pin "2") (pinfunction "COIL_1_2") (pintype "passive"))
      (node (ref "Q13") (pin "1") (pinfunction "E_1") (pintype "passive"))
      (node (ref "R58") (pin "2") (pinfunction "2_2") (pintype "passive"))
    )
    (net (code "63") (name "Net-(D32-C)") (class "Default")
      (node (ref "D32") (pin "1") (pinfunction "C_1") (pintype "passive"))
      (node (ref "R58") (pin "1") (pinfunction "1_1") (pintype "passive"))
    )
    (net (code "64") (name "Net-(D33-A)") (class "Default")
      (node (ref "D33") (pin "2") (pinfunction "A_2") (pintype "passive"))
      (node (ref "K14") (pin "2") (pinfunction "COIL_1_2") (pintype "passive"))
      (node (ref "Q14") (pin "1") (pinfunction "E_1") (pintype "passive"))
      (node (ref "R59") (pin "2") (pinfunction "2_2") (pintype "passive"))
    )
    (net (code "65") (name "Net-(D34-C)") (class "Default")
      (node (ref "D34") (pin "1") (pinfunction "C_1") (pintype "passive"))
      (node (ref "R59") (pin "1") (pinfunction "1_1") (pintype "passive"))
    )
    (net (code "66") (name "Net-(D35-A)") (class "Default")
      (node (ref "D35") (pin "2") (pinfunction "A_2") (pintype "passive"))
      (node (ref "K15") (pin "2") (pinfunction "COIL_1_2") (pintype "passive"))
      (node (ref "Q15") (pin "1") (pinfunction "E_1") (pintype "passive"))
      (node (ref "R63") (pin "2") (pinfunction "2_2") (pintype "passive"))
    )
    (net (code "67") (name "Net-(D36-C)") (class "Default")
      (node (ref "D36") (pin "1") (pinfunction "C_1") (pintype "passive"))
      (node (ref "R63") (pin "1") (pinfunction "1_1") (pintype "passive"))
    )
    (net (code "68") (name "Net-(OP1-A)") (class "Default")
      (node (ref "OP1") (pin "1") (pinfunction "A_1") (pintype "passive"))
      (node (ref "R28") (pin "2") (pinfunction "2_2") (pintype "passive"))
    )
    (net (code "69") (name "Net-(OP1-C-Pad4)") (class "Default")
      (node (ref "OP1") (pin "4") (pinfunction "C_4") (pintype "passive"))
      (node (ref "R1") (pin "2") (pinfunction "2_2") (pintype "passive"))
      (node (ref "R31") (pin "1") (pinfunction "1_1") (pintype "passive"))
    )
    (net (code "70") (name "Net-(OP2-A)") (class "Default")
      (node (ref "OP2") (pin "1") (pinfunction "A_1") (pintype "passive"))
      (node (ref "R2") (pin "2") (pinfunction "2_2") (pintype "passive"))
    )
    (net (code "71") (name "Net-(OP2-C-Pad4)") (class "Default")
      (node (ref "OP2") (pin "4") (pinfunction "C_4") (pintype "passive"))
      (node (ref "R3") (pin "2") (pinfunction "2_2") (pintype "passive"))
      (node (ref "R32") (pin "1") (pinfunction "1_1") (pintype "passive"))
    )
    (net (code "72") (name "Net-(OP3-A)") (class "Default")
      (node (ref "OP3") (pin "1") (pinfunction "A_1") (pintype "passive"))
      (node (ref "R30") (pin "2") (pinfunction "2_2") (pintype "passive"))
    )
    (net (code "73") (name "Net-(OP3-C-Pad4)") (class "Default")
      (node (ref "OP3") (pin "4") (pinfunction "C_4") (pintype "passive"))
      (node (ref "R10") (pin "2") (pinfunction "2_2") (pintype "passive"))
      (node (ref "R36") (pin "1") (pinfunction "1_1") (pintype "passive"))
    )
    (net (code "74") (name "Net-(OP4-A)") (class "Default")
      (node (ref "OP4") (pin "1") (pinfunction "A_1") (pintype "passive"))
      (node (ref "R33") (pin "2") (pinfunction "2_2") (pintype "passive"))
    )
    (net (code "75") (name "Net-(OP4-C-Pad4)") (class "Default")
      (node (ref "OP4") (pin "4") (pinfunction "C_4") (pintype "passive"))
      (node (ref "R37") (pin "1") (pinfunction "1_1") (pintype "passive"))
      (node (ref "R4") (pin "2") (pinfunction "2_2") (pintype "passive"))
    )
    (net (code "76") (name "Net-(OP5-A)") (class "Default")
      (node (ref "OP5") (pin "1") (pinfunction "A_1") (pintype "passive"))
      (node (ref "R34") (pin "2") (pinfunction "2_2") (pintype "passive"))
    )
    (net (code "77") (name "Net-(OP5-C-Pad4)") (class "Default")
      (node (ref "OP5") (pin "4") (pinfunction "C_4") (pintype "passive"))
      (node (ref "R38") (pin "1") (pinfunction "1_1") (pintype "passive"))
      (node (ref "R5") (pin "2") (pinfunction "2_2") (pintype "passive"))
    )
    (net (code "78") (name "Net-(OP6-A)") (class "Default")
      (node (ref "OP6") (pin "1") (pinfunction "A_1") (pintype "passive"))
      (node (ref "R35") (pin "2") (pinfunction "2_2") (pintype "passive"))
    )
    (net (code "79") (name "Net-(OP6-C-Pad4)") (class "Default")
      (node (ref "OP6") (pin "4") (pinfunction "C_4") (pintype "passive"))
      (node (ref "R39") (pin "1") (pinfunction "1_1") (pintype "passive"))
      (node (ref "R6") (pin "2") (pinfunction "2_2") (pintype "passive"))
    )
    (net (code "80") (name "Net-(OP7-A)") (class "Default")
      (node (ref "OP7") (pin "1") (pinfunction "A_1") (pintype "passive"))
      (node (ref "R46") (pin "2") (pinfunction "2_2") (pintype "passive"))
    )
    (net (code "81") (name "Net-(OP7-C-Pad4)") (class "Default")
      (node (ref "OP7") (pin "4") (pinfunction "C_4") (pintype "passive"))
      (node (ref "R13") (pin "2") (pinfunction "2_2") (pintype "passive"))
      (node (ref "R45") (pin "1") (pinfunction "1_1") (pintype "passive"))
    )
    (net (code "82") (name "Net-(OP8-A)") (class "Default")
      (node (ref "OP8") (pin "1") (pinfunction "A_1") (pintype "passive"))
      (node (ref "R51") (pin "2") (pinfunction "2_2") (pintype "passive"))
    )
    (net (code "83") (name "Net-(OP8-C-Pad4)") (class "Default")
      (node (ref "OP8") (pin "4") (pinfunction "C_4") (pintype "passive"))
      (node (ref "R14") (pin "2") (pinfunction "2_2") (pintype "passive"))
      (node (ref "R42") (pin "1") (pinfunction "1_1") (pintype "passive"))
    )
    (net (code "84") (name "Net-(OP9-A)") (class "Default")
      (node (ref "OP9") (pin "1") (pinfunction "A_1") (pintype "passive"))
      (node (ref "R15") (pin "2") (pinfunction "2_2") (pintype "passive"))
    )
    (net (code "85") (name "Net-(OP9-C-Pad4)") (class "Default")
      (node (ref "OP9") (pin "4") (pinfunction "C_4") (pintype "passive"))
      (node (ref "R44") (pin "1") (pinfunction "1_1") (pintype "passive"))
      (node (ref "R48") (pin "2") (pinfunction "2_2") (pintype "passive"))
    )
    (net (code "86") (name "Net-(OP10-A)") (class "Default")
      (node (ref "OP10") (pin "1") (pinfunction "A_1") (pintype "passive"))
      (node (ref "R16") (pin "2") (pinfunction "2_2") (pintype "passive"))
    )
    (net (code "87") (name "Net-(OP10-C-Pad4)") (class "Default")
      (node (ref "OP10") (pin "4") (pinfunction "C_4") (pintype "passive"))
      (node (ref "R43") (pin "1") (pinfunction "1_1") (pintype "passive"))
      (node (ref "R47") (pin "2") (pinfunction "2_2") (pintype "passive"))
    )
    (net (code "88") (name "Net-(OP11-A)") (class "Default")
      (node (ref "OP11") (pin "1") (pinfunction "A_1") (pintype "passive"))
      (node (ref "R17") (pin "2") (pinfunction "2_2") (pintype "passive"))
    )
    (net (code "89") (name "Net-(OP11-C-Pad4)") (class "Default")
      (node (ref "OP11") (pin "4") (pinfunction "C_4") (pintype "passive"))
      (node (ref "R40") (pin "1") (pinfunction "1_1") (pintype "passive"))
      (node (ref "R55") (pin "2") (pinfunction "2_2") (pintype "passive"))
    )
    (net (code "90") (name "Net-(OP12-A)") (class "Default")
      (node (ref "OP12") (pin "1") (pinfunction "A_1") (pintype "passive"))
      (node (ref "R18") (pin "2") (pinfunction "2_2") (pintype "passive"))
    )
    (net (code "91") (name "Net-(OP12-C-Pad4)") (class "Default")
      (node (ref "OP12") (pin "4") (pinfunction "C_4") (pintype "passive"))
      (node (ref "R41") (pin "1") (pinfunction "1_1") (pintype "passive"))
      (node (ref "R50") (pin "2") (pinfunction "2_2") (pintype "passive"))
    )
    (net (code "92") (name "Net-(OP13-A)") (class "Default")
      (node (ref "OP13") (pin "1") (pinfunction "A_1") (pintype "passive"))
      (node (ref "R53") (pin "2") (pinfunction "2_2") (pintype "passive"))
    )
    (net (code "93") (name "Net-(OP13-C-Pad4)") (class "Default")
      (node (ref "OP13") (pin "4") (pinfunction "C_4") (pintype "passive"))
      (node (ref "R49") (pin "1") (pinfunction "1_1") (pintype "passive"))
      (node (ref "R56") (pin "2") (pinfunction "2_2") (pintype "passive"))
    )
    (net (code "94") (name "Net-(OP14-A)") (class "Default")
      (node (ref "OP14") (pin "1") (pinfunction "A_1") (pintype "passive"))
      (node (ref "R54") (pin "2") (pinfunction "2_2") (pintype "passive"))
    )
    (net (code "95") (name "Net-(OP14-C-Pad4)") (class "Default")
      (node (ref "OP14") (pin "4") (pinfunction "C_4") (pintype "passive"))
      (node (ref "R52") (pin "1") (pinfunction "1_1") (pintype "passive"))
      (node (ref "R57") (pin "2") (pinfunction "2_2") (pintype "passive"))
    )
    (net (code "96") (name "Net-(OP15-A)") (class "Default")
      (node (ref "OP15") (pin "1") (pinfunction "A_1") (pintype "passive"))
      (node (ref "R61") (pin "2") (pinfunction "2_2") (pintype "passive"))
    )
    (net (code "97") (name "Net-(OP15-C-Pad4)") (class "Default")
      (node (ref "OP15") (pin "4") (pinfunction "C_4") (pintype "passive"))
      (node (ref "R60") (pin "1") (pinfunction "1_1") (pintype "passive"))
      (node (ref "R62") (pin "2") (pinfunction "2_2") (pintype "passive"))
    )
    (net (code "98") (name "Net-(Q1-B)") (class "Default")
      (node (ref "Q1") (pin "3") (pinfunction "B_3") (pintype "passive"))
      (node (ref "R1") (pin "1") (pinfunction "1_1") (pintype "passive"))
    )
    (net (code "99") (name "Net-(Q2-B)") (class "Default")
      (node (ref "Q2") (pin "3") (pinfunction "B_3") (pintype "passive"))
      (node (ref "R3") (pin "1") (pinfunction "1_1") (pintype "passive"))
    )
    (net (code "100") (name "Net-(Q3-B)") (class "Default")
      (node (ref "Q3") (pin "3") (pinfunction "B_3") (pintype "passive"))
      (node (ref "R10") (pin "1") (pinfunction "1_1") (pintype "passive"))
    )
    (net (code "101") (name "Net-(Q4-B)") (class "Default")
      (node (ref "Q4") (pin "3") (pinfunction "B_3") (pintype "passive"))
      (node (ref "R4") (pin "1") (pinfunction "1_1") (pintype "passive"))
    )
    (net (code "102") (name "Net-(Q5-B)") (class "Default")
      (node (ref "Q5") (pin "3") (pinfunction "B_3") (pintype "passive"))
      (node (ref "R5") (pin "1") (pinfunction "1_1") (pintype "passive"))
    )
    (net (code "103") (name "Net-(Q6-B)") (class "Default")
      (node (ref "Q6") (pin "3") (pinfunction "B_3") (pintype "passive"))
      (node (ref "R6") (pin "1") (pinfunction "1_1") (pintype "passive"))
    )
    (net (code "104") (name "Net-(Q7-B)") (class "Default")
      (node (ref "Q7") (pin "3") (pinfunction "B_3") (pintype "passive"))
      (node (ref "R13") (pin "1") (pinfunction "1_1") (pintype "passive"))
    )
    (net (code "105") (name "Net-(Q8-B)") (class "Default")
      (node (ref "Q8") (pin "3") (pinfunction "B_3") (pintype "passive"))
      (node (ref "R14") (pin "1") (pinfunction "1_1") (pintype "passive"))
    )
    (net (code "106") (name "Net-(Q9-B)") (class "Default")
      (node (ref "Q9") (pin "3") (pinfunction "B_3") (pintype "passive"))
      (node (ref "R48") (pin "1") (pinfunction "1_1") (pintype "passive"))
    )
    (net (code "107") (name "Net-(Q10-B)") (class "Default")
      (node (ref "Q10") (pin "3") (pinfunction "B_3") (pintype "passive"))
      (node (ref "R47") (pin "1") (pinfunction "1_1") (pintype "passive"))
    )
    (net (code "108") (name "Net-(Q11-B)") (class "Default")
      (node (ref "Q11") (pin "3") (pinfunction "B_3") (pintype "passive"))
      (node (ref "R55") (pin "1") (pinfunction "1_1") (pintype "passive"))
    )
    (net (code "109") (name "Net-(Q12-B)") (class "Default")
      (node (ref "Q12") (pin "3") (pinfunction "B_3") (pintype "passive"))
      (node (ref "R50") (pin "1") (pinfunction "1_1") (pintype "passive"))
    )
    (net (code "110") (name "Net-(Q13-B)") (class "Default")
      (node (ref "Q13") (pin "3") (pinfunction "B_3") (pintype "passive"))
      (node (ref "R56") (pin "1") (pinfunction "1_1") (pintype "passive"))
    )
    (net (code "111") (name "Net-(Q14-B)") (class "Default")
      (node (ref "Q14") (pin "3") (pinfunction "B_3") (pintype "passive"))
      (node (ref "R57") (pin "1") (pinfunction "1_1") (pintype "passive"))
    )
    (net (code "112") (name "Net-(Q15-B)") (class "Default")
      (node (ref "Q15") (pin "3") (pinfunction "B_3") (pintype "passive"))
      (node (ref "R62") (pin "1") (pinfunction "1_1") (pintype "passive"))
    )
    (net (code "113") (name "Net-(U1-FB)") (class "Default")
      (node (ref "R25") (pin "2") (pinfunction "2_2") (pintype "passive"))
      (node (ref "R27") (pin "1") (pinfunction "1_1") (pintype "passive"))
      (node (ref "U1") (pin "4") (pinfunction "FB_4") (pintype "input"))
    )
    (net (code "114") (name "unconnected-(K1-NO-Pad3)") (class "Default")
      (node (ref "K1") (pin "3") (pinfunction "NO_3") (pintype "passive+no_connect"))
    )
    (net (code "115") (name "unconnected-(K2-NO-Pad3)") (class "Default")
      (node (ref "K2") (pin "3") (pinfunction "NO_3") (pintype "passive+no_connect"))
    )
    (net (code "116") (name "unconnected-(K3-NO-Pad3)") (class "Default")
      (node (ref "K3") (pin "3") (pinfunction "NO_3") (pintype "passive+no_connect"))
    )
    (net (code "117") (name "unconnected-(K4-NO-Pad3)") (class "Default")
      (node (ref "K4") (pin "3") (pinfunction "NO_3") (pintype "passive+no_connect"))
    )
    (net (code "118") (name "unconnected-(K5-NO-Pad3)") (class "Default")
      (node (ref "K5") (pin "3") (pinfunction "NO_3") (pintype "passive+no_connect"))
    )
    (net (code "119") (name "unconnected-(K6-NO-Pad3)") (class "Default")
      (node (ref "K6") (pin "3") (pinfunction "NO_3") (pintype "passive+no_connect"))
    )
    (net (code "120") (name "unconnected-(K7-NO-Pad3)") (class "Default")
      (node (ref "K7") (pin "3") (pinfunction "NO_3") (pintype "passive+no_connect"))
    )
    (net (code "121") (name "unconnected-(K8-NO-Pad3)") (class "Default")
      (node (ref "K8") (pin "3") (pinfunction "NO_3") (pintype "passive+no_connect"))
    )
    (net (code "122") (name "unconnected-(K9-NO-Pad3)") (class "Default")
      (node (ref "K9") (pin "3") (pinfunction "NO_3") (pintype "passive+no_connect"))
    )
    (net (code "123") (name "unconnected-(K10-NO-Pad3)") (class "Default")
      (node (ref "K10") (pin "3") (pinfunction "NO_3") (pintype "passive+no_connect"))
    )
    (net (code "124") (name "unconnected-(K11-NO-Pad3)") (class "Default")
      (node (ref "K11") (pin "3") (pinfunction "NO_3") (pintype "passive+no_connect"))
    )
    (net (code "125") (name "unconnected-(K12-NO-Pad3)") (class "Default")
      (node (ref "K12") (pin "3") (pinfunction "NO_3") (pintype "passive+no_connect"))
    )
    (net (code "126") (name "unconnected-(K13-NO-Pad3)") (class "Default")
      (node (ref "K13") (pin "3") (pinfunction "NO_3") (pintype "passive+no_connect"))
    )
    (net (code "127") (name "unconnected-(K14-NO-Pad3)") (class "Default")
      (node (ref "K14") (pin "3") (pinfunction "NO_3") (pintype "passive+no_connect"))
    )
    (net (code "128") (name "unconnected-(K15-NO-Pad3)") (class "Default")
      (node (ref "K15") (pin "3") (pinfunction "NO_3") (pintype "passive+no_connect"))
    )
    (net (code "129") (name "~24V") (class "Default")
      (node (ref "D25") (pin "1") (pinfunction "K_1") (pintype "passive"))
      (node (ref "D26") (pin "1") (pinfunction "K_1") (pintype "passive"))
      (node (ref "X4") (pin "4") (pinfunction "4_4") (pintype "passive"))
    )
    (net (code "130") (name "~24V.") (class "Default")
      (node (ref "D29") (pin "2") (pinfunction "A_2") (pintype "passive"))
      (node (ref "D30") (pin "2") (pinfunction "A_2") (pintype "passive"))
      (node (ref "X4") (pin "5") (pinfunction "5_5") (pintype "passive"))
    )
  )
)
